# robot_board.net
KiCad netlist of a schematic drawn in EAGLE
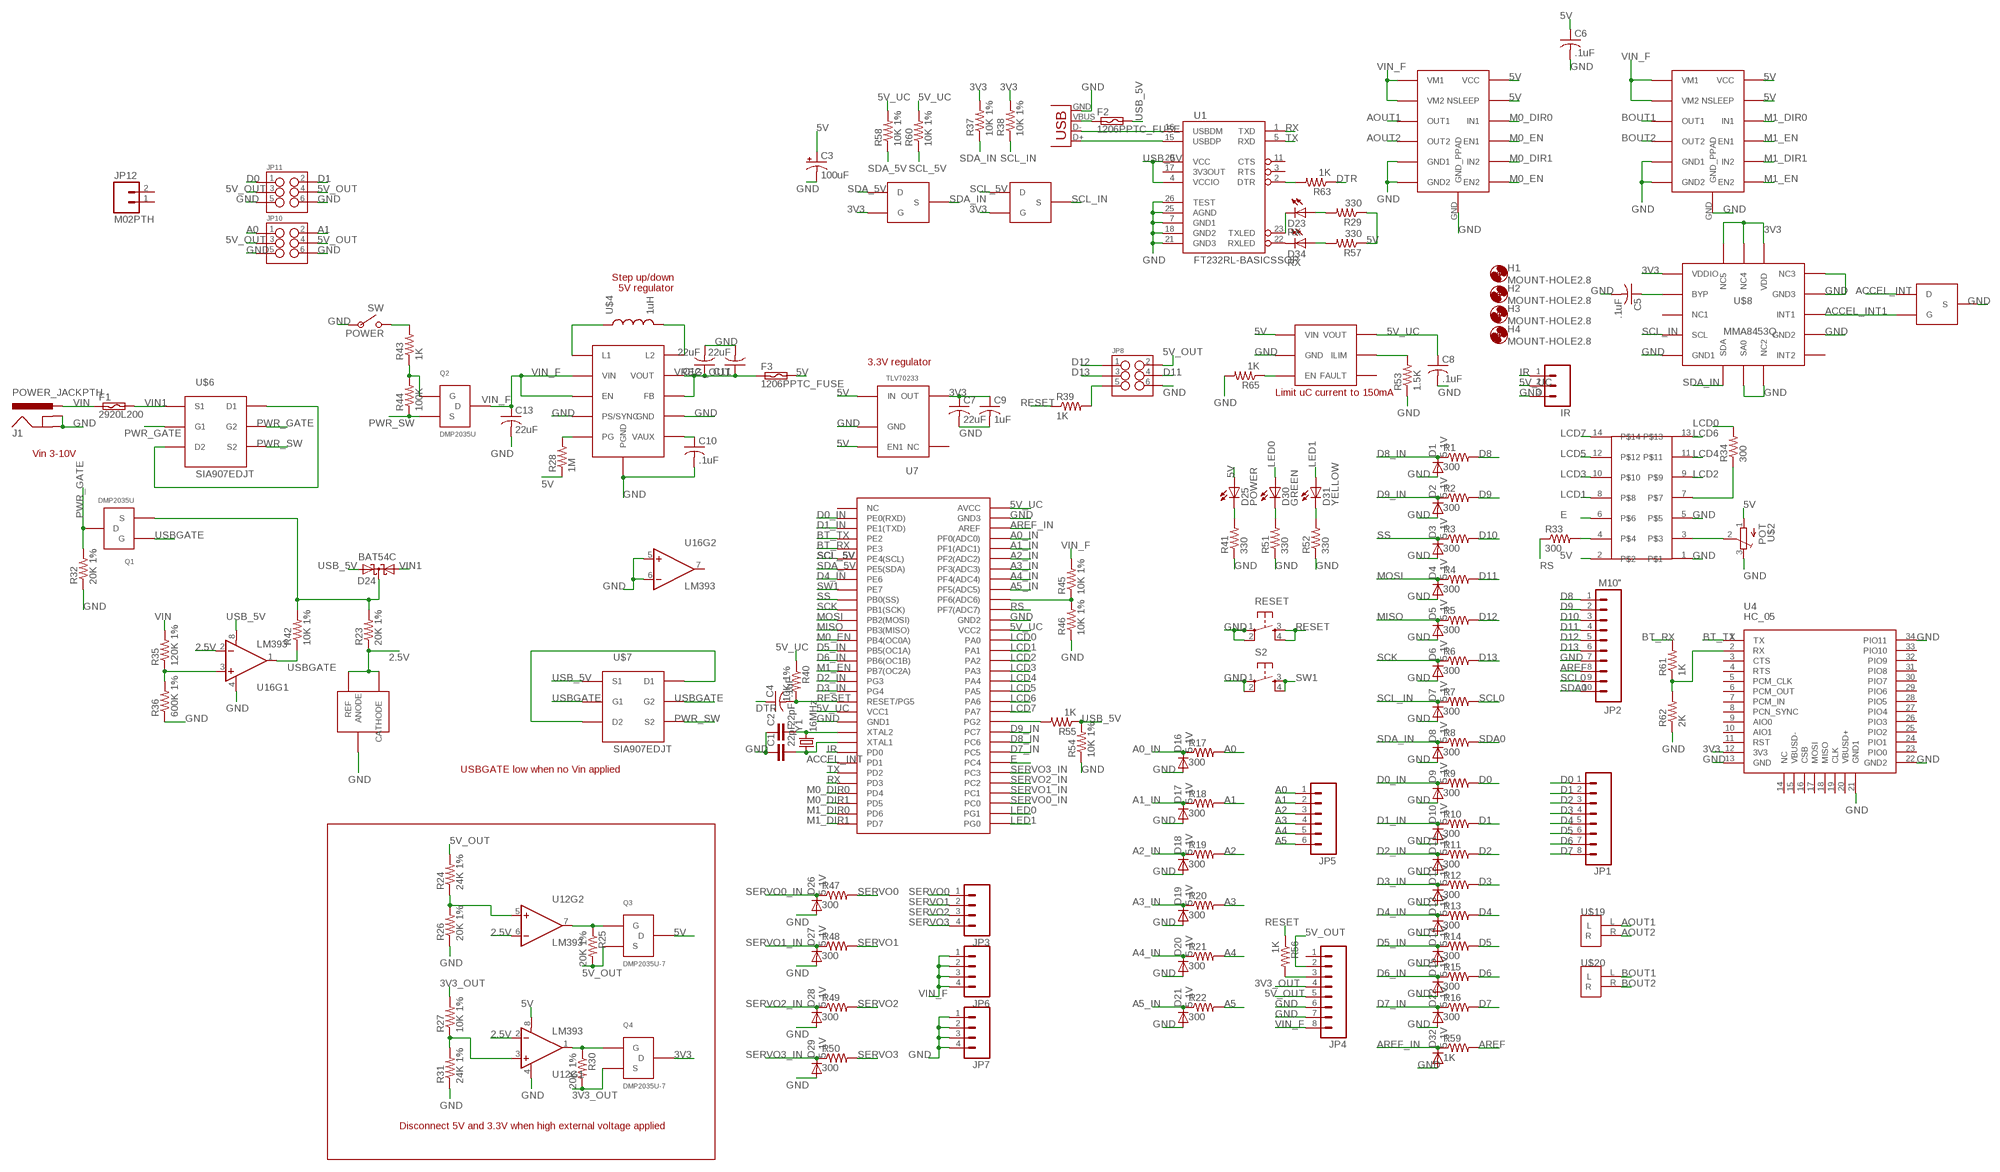
[diagram p0: schematic, sheet 1]

(export (version "E")
  (design (tool "Eeschema 10.0.6"))
  (components
    (comp (ref "C1")
      (value "22pF")
      (footprint "eagle-import:0805")
      (libsource (lib "eagle-import") (part "CAP0805"))
    )
    (comp (ref "C2")
      (value "22pF")
      (footprint "eagle-import:0805")
      (libsource (lib "eagle-import") (part "CAP0805"))
    )
    (comp (ref "C3")
      (value "100uF")
      (footprint "eagle-import:PANASONIC_D")
      (libsource (lib "eagle-import") (part "CAP_POLD"))
    )
    (comp (ref "C4")
      (value ".1uF")
      (footprint "eagle-import:C1206")
      (libsource (lib "eagle-import") (part "C-USC1206"))
    )
    (comp (ref "C5")
      (value ".1uF")
      (footprint "eagle-import:C1206")
      (libsource (lib "eagle-import") (part "C-USC1206"))
    )
    (comp (ref "C6")
      (value ".1uF")
      (footprint "eagle-import:C1206")
      (libsource (lib "eagle-import") (part "C-USC1206"))
    )
    (comp (ref "C7")
      (value "22uF")
      (footprint "eagle-import:C1206")
      (libsource (lib "eagle-import") (part "C-USC1206"))
    )
    (comp (ref "C8")
      (value ".1uF")
      (footprint "eagle-import:C1206")
      (libsource (lib "eagle-import") (part "C-USC1206"))
    )
    (comp (ref "C9")
      (value "1uF")
      (footprint "eagle-import:C1206")
      (libsource (lib "eagle-import") (part "C-USC1206"))
    )
    (comp (ref "C10")
      (value ".1uF")
      (footprint "eagle-import:C1206")
      (libsource (lib "eagle-import") (part "C-USC1206"))
    )
    (comp (ref "C11")
      (value "22uF")
      (footprint "eagle-import:C1206")
      (libsource (lib "eagle-import") (part "C-USC1206"))
    )
    (comp (ref "C12")
      (value "22uF")
      (footprint "eagle-import:C1206")
      (libsource (lib "eagle-import") (part "C-USC1206"))
    )
    (comp (ref "C13")
      (value "22uF")
      (footprint "eagle-import:C1206")
      (libsource (lib "eagle-import") (part "C-USC1206"))
    )
    (comp (ref "D1")
      (value "5.1V")
      (footprint "eagle-import:SOT23-3")
      (libsource (lib "eagle-import") (part "DIODESOT23"))
    )
    (comp (ref "D2")
      (value "5.1V")
      (footprint "eagle-import:SOT23-3")
      (libsource (lib "eagle-import") (part "DIODESOT23"))
    )
    (comp (ref "D3")
      (value "5.1V")
      (footprint "eagle-import:SOT23-3")
      (libsource (lib "eagle-import") (part "DIODESOT23"))
    )
    (comp (ref "D4")
      (value "5.1V")
      (footprint "eagle-import:SOT23-3")
      (libsource (lib "eagle-import") (part "DIODESOT23"))
    )
    (comp (ref "D5")
      (value "5.1V")
      (footprint "eagle-import:SOT23-3")
      (libsource (lib "eagle-import") (part "DIODESOT23"))
    )
    (comp (ref "D6")
      (value "5.1V")
      (footprint "eagle-import:SOT23-3")
      (libsource (lib "eagle-import") (part "DIODESOT23"))
    )
    (comp (ref "D7")
      (value "5.1V")
      (footprint "eagle-import:SOT23-3")
      (libsource (lib "eagle-import") (part "DIODESOT23"))
    )
    (comp (ref "D8")
      (value "5.1V")
      (footprint "eagle-import:SOT23-3")
      (libsource (lib "eagle-import") (part "DIODESOT23"))
    )
    (comp (ref "D9")
      (value "5.1V")
      (footprint "eagle-import:SOT23-3")
      (libsource (lib "eagle-import") (part "DIODESOT23"))
    )
    (comp (ref "D10")
      (value "5.1V")
      (footprint "eagle-import:SOT23-3")
      (libsource (lib "eagle-import") (part "DIODESOT23"))
    )
    (comp (ref "D11")
      (value "5.1V")
      (footprint "eagle-import:SOT23-3")
      (libsource (lib "eagle-import") (part "DIODESOT23"))
    )
    (comp (ref "D12")
      (value "5.1V")
      (footprint "eagle-import:SOT23-3")
      (libsource (lib "eagle-import") (part "DIODESOT23"))
    )
    (comp (ref "D13")
      (value "5.1V")
      (footprint "eagle-import:SOT23-3")
      (libsource (lib "eagle-import") (part "DIODESOT23"))
    )
    (comp (ref "D14")
      (value "5.1V")
      (footprint "eagle-import:SOT23-3")
      (libsource (lib "eagle-import") (part "DIODESOT23"))
    )
    (comp (ref "D15")
      (value "5.1V")
      (footprint "eagle-import:SOT23-3")
      (libsource (lib "eagle-import") (part "DIODESOT23"))
    )
    (comp (ref "D16")
      (value "5.1V")
      (footprint "eagle-import:SOT23-3")
      (libsource (lib "eagle-import") (part "DIODESOT23"))
    )
    (comp (ref "D17")
      (value "5.1V")
      (footprint "eagle-import:SOT23-3")
      (libsource (lib "eagle-import") (part "DIODESOT23"))
    )
    (comp (ref "D18")
      (value "5.1V")
      (footprint "eagle-import:SOT23-3")
      (libsource (lib "eagle-import") (part "DIODESOT23"))
    )
    (comp (ref "D19")
      (value "5.1V")
      (footprint "eagle-import:SOT23-3")
      (libsource (lib "eagle-import") (part "DIODESOT23"))
    )
    (comp (ref "D20")
      (value "5.1V")
      (footprint "eagle-import:SOT23-3")
      (libsource (lib "eagle-import") (part "DIODESOT23"))
    )
    (comp (ref "D21")
      (value "5.1V")
      (footprint "eagle-import:SOT23-3")
      (libsource (lib "eagle-import") (part "DIODESOT23"))
    )
    (comp (ref "D22")
      (value "5.1V")
      (footprint "eagle-import:SOT23-3")
      (libsource (lib "eagle-import") (part "DIODESOT23"))
    )
    (comp (ref "D23")
      (value "RX")
      (footprint "eagle-import:LED-1206")
      (libsource (lib "eagle-import") (part "LED-GREENLILYPAD"))
    )
    (comp (ref "D24")
      (value "BAT54C")
      (footprint "eagle-import:SOT23")
      (libsource (lib "eagle-import") (part "BAT54C"))
    )
    (comp (ref "D25")
      (value "POWER")
      (footprint "eagle-import:LED-1206")
      (libsource (lib "eagle-import") (part "LED-GREENLILYPAD"))
    )
    (comp (ref "D26")
      (value "5.1V")
      (footprint "eagle-import:SOT23-3")
      (libsource (lib "eagle-import") (part "DIODESOT23"))
    )
    (comp (ref "D27")
      (value "5.1V")
      (footprint "eagle-import:SOT23-3")
      (libsource (lib "eagle-import") (part "DIODESOT23"))
    )
    (comp (ref "D28")
      (value "5.1V")
      (footprint "eagle-import:SOT23-3")
      (libsource (lib "eagle-import") (part "DIODESOT23"))
    )
    (comp (ref "D29")
      (value "5.1V")
      (footprint "eagle-import:SOT23-3")
      (libsource (lib "eagle-import") (part "DIODESOT23"))
    )
    (comp (ref "D30")
      (value "GREEN")
      (footprint "eagle-import:LED-1206")
      (libsource (lib "eagle-import") (part "LED-GREENLILYPAD"))
    )
    (comp (ref "D31")
      (value "YELLOW")
      (footprint "eagle-import:LED-1206")
      (libsource (lib "eagle-import") (part "LED-GREENLILYPAD"))
    )
    (comp (ref "D32")
      (value "5.1V")
      (footprint "eagle-import:SOT23-3")
      (libsource (lib "eagle-import") (part "DIODESOT23"))
    )
    (comp (ref "D34")
      (value "RX")
      (footprint "eagle-import:LED-1206")
      (libsource (lib "eagle-import") (part "LED-GREENLILYPAD"))
    )
    (comp (ref "F1")
      (value "2920L200")
      (footprint "eagle-import:SMD050F")
      (libsource (lib "eagle-import") (part "2920L200"))
    )
    (comp (ref "F2")
      (value "1206PPTC_FUSE")
      (footprint "eagle-import:R1206")
      (libsource (lib "eagle-import") (part "1206PPTC_FUSE"))
    )
    (comp (ref "F3")
      (value "1206PPTC_FUSE")
      (footprint "eagle-import:R1206")
      (libsource (lib "eagle-import") (part "1206PPTC_FUSE"))
    )
    (comp (ref "H1")
      (value "MOUNT-HOLE2.8")
      (footprint "eagle-import:2,8")
      (libsource (lib "eagle-import") (part "MOUNT-HOLE2.8"))
    )
    (comp (ref "H2")
      (value "MOUNT-HOLE2.8")
      (footprint "eagle-import:2,8")
      (libsource (lib "eagle-import") (part "MOUNT-HOLE2.8"))
    )
    (comp (ref "H3")
      (value "MOUNT-HOLE2.8")
      (footprint "eagle-import:2,8")
      (libsource (lib "eagle-import") (part "MOUNT-HOLE2.8"))
    )
    (comp (ref "H4")
      (value "MOUNT-HOLE2.8")
      (footprint "eagle-import:2,8")
      (libsource (lib "eagle-import") (part "MOUNT-HOLE2.8"))
    )
    (comp (ref "IR")
      (value "M03PTH")
      (footprint "eagle-import:1X03")
      (libsource (lib "eagle-import") (part "M03PTH"))
    )
    (comp (ref "J1")
      (value "POWER_JACKPTH")
      (footprint "eagle-import:POWER_JACK_PTH")
      (libsource (lib "eagle-import") (part "POWER_JACKPTH"))
    )
    (comp (ref "JP1")
      (value "M081X08")
      (footprint "eagle-import:1X08")
      (libsource (lib "eagle-import") (part "M081X08"))
    )
    (comp (ref "JP2")
      (value "M10\"")
      (footprint "eagle-import:1X10")
      (libsource (lib "eagle-import") (part "M10{dblquote}"))
    )
    (comp (ref "JP3")
      (value "M04PTH")
      (footprint "eagle-import:1X04")
      (libsource (lib "eagle-import") (part "M04PTH"))
    )
    (comp (ref "JP4")
      (value "M081X08")
      (footprint "eagle-import:1X08")
      (libsource (lib "eagle-import") (part "M081X08"))
    )
    (comp (ref "JP5")
      (value "M06SIP")
      (footprint "eagle-import:1X06")
      (libsource (lib "eagle-import") (part "M06SIP"))
    )
    (comp (ref "JP6")
      (value "M04PTH")
      (footprint "eagle-import:1X04")
      (libsource (lib "eagle-import") (part "M04PTH"))
    )
    (comp (ref "JP7")
      (value "M04PTH")
      (footprint "eagle-import:1X04")
      (libsource (lib "eagle-import") (part "M04PTH"))
    )
    (comp (ref "JP8")
      (value "M03X22X3_SILK_SM")
      (footprint "eagle-import:2X3")
      (libsource (lib "eagle-import") (part "M03X22X3_SILK_SM"))
    )
    (comp (ref "JP9")
      (value "USB-B")
      (footprint "eagle-import:USB-B-PTH")
      (libsource (lib "eagle-import") (part "USBPTH"))
    )
    (comp (ref "JP10")
      (value "M03X22X3_SILK_SM")
      (footprint "eagle-import:2X3")
      (libsource (lib "eagle-import") (part "M03X22X3_SILK_SM"))
    )
    (comp (ref "JP11")
      (value "M03X22X3_SILK_SM")
      (footprint "eagle-import:2X3")
      (libsource (lib "eagle-import") (part "M03X22X3_SILK_SM"))
    )
    (comp (ref "JP12")
      (value "M02PTH")
      (footprint "eagle-import:1X02")
      (libsource (lib "eagle-import") (part "M02PTH"))
    )
    (comp (ref "POWER")
      (value "SW")
      (footprint "eagle-import:SW")
      (libsource (lib "eagle-import") (part "SW"))
    )
    (comp (ref "Q1")
      (value "DMP2035U")
      (footprint "eagle-import:SOT23")
      (libsource (lib "eagle-import") (part "DMP2035U"))
    )
    (comp (ref "Q2")
      (value "DMP2035U")
      (footprint "eagle-import:SOT23")
      (libsource (lib "eagle-import") (part "DMP2035U"))
    )
    (comp (ref "Q3")
      (value "DMP2035U-7")
      (footprint "eagle-import:SOT23@1")
      (libsource (lib "eagle-import") (part "DMP2035U-7"))
    )
    (comp (ref "Q4")
      (value "DMP2035U-7")
      (footprint "eagle-import:SOT23@1")
      (libsource (lib "eagle-import") (part "DMP2035U-7"))
    )
    (comp (ref "R1")
      (value "300")
      (footprint "eagle-import:R1206")
      (libsource (lib "eagle-import") (part "R-US_R1206"))
    )
    (comp (ref "R2")
      (value "300")
      (footprint "eagle-import:R1206")
      (libsource (lib "eagle-import") (part "R-US_R1206"))
    )
    (comp (ref "R3")
      (value "300")
      (footprint "eagle-import:R1206")
      (libsource (lib "eagle-import") (part "R-US_R1206"))
    )
    (comp (ref "R4")
      (value "300")
      (footprint "eagle-import:R1206")
      (libsource (lib "eagle-import") (part "R-US_R1206"))
    )
    (comp (ref "R5")
      (value "300")
      (footprint "eagle-import:R1206")
      (libsource (lib "eagle-import") (part "R-US_R1206"))
    )
    (comp (ref "R6")
      (value "300")
      (footprint "eagle-import:R1206")
      (libsource (lib "eagle-import") (part "R-US_R1206"))
    )
    (comp (ref "R7")
      (value "300")
      (footprint "eagle-import:R1206")
      (libsource (lib "eagle-import") (part "R-US_R1206"))
    )
    (comp (ref "R8")
      (value "300")
      (footprint "eagle-import:R1206")
      (libsource (lib "eagle-import") (part "R-US_R1206"))
    )
    (comp (ref "R9")
      (value "300")
      (footprint "eagle-import:R1206")
      (libsource (lib "eagle-import") (part "R-US_R1206"))
    )
    (comp (ref "R10")
      (value "300")
      (footprint "eagle-import:R1206")
      (libsource (lib "eagle-import") (part "R-US_R1206"))
    )
    (comp (ref "R11")
      (value "300")
      (footprint "eagle-import:R1206")
      (libsource (lib "eagle-import") (part "R-US_R1206"))
    )
    (comp (ref "R12")
      (value "300")
      (footprint "eagle-import:R1206")
      (libsource (lib "eagle-import") (part "R-US_R1206"))
    )
    (comp (ref "R13")
      (value "300")
      (footprint "eagle-import:R1206")
      (libsource (lib "eagle-import") (part "R-US_R1206"))
    )
    (comp (ref "R14")
      (value "300")
      (footprint "eagle-import:R1206")
      (libsource (lib "eagle-import") (part "R-US_R1206"))
    )
    (comp (ref "R15")
      (value "300")
      (footprint "eagle-import:R1206")
      (libsource (lib "eagle-import") (part "R-US_R1206"))
    )
    (comp (ref "R16")
      (value "300")
      (footprint "eagle-import:R1206")
      (libsource (lib "eagle-import") (part "R-US_R1206"))
    )
    (comp (ref "R17")
      (value "300")
      (footprint "eagle-import:R1206")
      (libsource (lib "eagle-import") (part "R-US_R1206"))
    )
    (comp (ref "R18")
      (value "300")
      (footprint "eagle-import:R1206")
      (libsource (lib "eagle-import") (part "R-US_R1206"))
    )
    (comp (ref "R19")
      (value "300")
      (footprint "eagle-import:R1206")
      (libsource (lib "eagle-import") (part "R-US_R1206"))
    )
    (comp (ref "R20")
      (value "300")
      (footprint "eagle-import:R1206")
      (libsource (lib "eagle-import") (part "R-US_R1206"))
    )
    (comp (ref "R21")
      (value "300")
      (footprint "eagle-import:R1206")
      (libsource (lib "eagle-import") (part "R-US_R1206"))
    )
    (comp (ref "R22")
      (value "300")
      (footprint "eagle-import:R1206")
      (libsource (lib "eagle-import") (part "R-US_R1206"))
    )
    (comp (ref "R23")
      (value "20K 1%")
      (footprint "eagle-import:R1206")
      (libsource (lib "eagle-import") (part "R-US_R1206"))
    )
    (comp (ref "R24")
      (value "24K 1%")
      (footprint "eagle-import:R1206")
      (libsource (lib "eagle-import") (part "R-US_R1206"))
    )
    (comp (ref "R25")
      (value "20K 1%")
      (footprint "eagle-import:R1206")
      (libsource (lib "eagle-import") (part "R-US_R1206"))
    )
    (comp (ref "R26")
      (value "20K 1%")
      (footprint "eagle-import:R1206")
      (libsource (lib "eagle-import") (part "R-US_R1206"))
    )
    (comp (ref "R27")
      (value "10K 1%")
      (footprint "eagle-import:R1206")
      (libsource (lib "eagle-import") (part "R-US_R1206"))
    )
    (comp (ref "R28")
      (value "1M")
      (footprint "eagle-import:R1206")
      (libsource (lib "eagle-import") (part "R-US_R1206"))
    )
    (comp (ref "R29")
      (value "330")
      (footprint "eagle-import:R1206")
      (libsource (lib "eagle-import") (part "R-US_R1206"))
    )
    (comp (ref "R30")
      (value "20K 1%")
      (footprint "eagle-import:R1206")
      (libsource (lib "eagle-import") (part "R-US_R1206"))
    )
    (comp (ref "R31")
      (value "24K 1%")
      (footprint "eagle-import:R1206")
      (libsource (lib "eagle-import") (part "R-US_R1206"))
    )
    (comp (ref "R32")
      (value "20K 1%")
      (footprint "eagle-import:R1206")
      (libsource (lib "eagle-import") (part "R-US_R1206"))
    )
    (comp (ref "R33")
      (value "300")
      (footprint "eagle-import:R1206")
      (libsource (lib "eagle-import") (part "R-US_R1206"))
    )
    (comp (ref "R34")
      (value "300")
      (footprint "eagle-import:R1206")
      (libsource (lib "eagle-import") (part "R-US_R1206"))
    )
    (comp (ref "R35")
      (value "120K 1%")
      (footprint "eagle-import:R1206")
      (libsource (lib "eagle-import") (part "R-US_R1206"))
    )
    (comp (ref "R36")
      (value "600K 1%")
      (footprint "eagle-import:R1206")
      (libsource (lib "eagle-import") (part "R-US_R1206"))
    )
    (comp (ref "R37")
      (value "10K 1%")
      (footprint "eagle-import:R1206")
      (libsource (lib "eagle-import") (part "R-US_R1206"))
    )
    (comp (ref "R38")
      (value "10K 1%")
      (footprint "eagle-import:R1206")
      (libsource (lib "eagle-import") (part "R-US_R1206"))
    )
    (comp (ref "R39")
      (value "1K")
      (footprint "eagle-import:R1206")
      (libsource (lib "eagle-import") (part "R-US_R1206"))
    )
    (comp (ref "R40")
      (value "10K 1%")
      (footprint "eagle-import:R1206")
      (libsource (lib "eagle-import") (part "R-US_R1206"))
    )
    (comp (ref "R41")
      (value "330")
      (footprint "eagle-import:R1206")
      (libsource (lib "eagle-import") (part "R-US_R1206"))
    )
    (comp (ref "R42")
      (value "10K 1%")
      (footprint "eagle-import:R1206")
      (libsource (lib "eagle-import") (part "R-US_R1206"))
    )
    (comp (ref "R43")
      (value "1K")
      (footprint "eagle-import:R1206")
      (libsource (lib "eagle-import") (part "R-US_R1206"))
    )
    (comp (ref "R44")
      (value "100K")
      (footprint "eagle-import:R1206")
      (libsource (lib "eagle-import") (part "R-US_R1206"))
    )
    (comp (ref "R45")
      (value "10K 1%")
      (footprint "eagle-import:R1206")
      (libsource (lib "eagle-import") (part "R-US_R1206"))
    )
    (comp (ref "R46")
      (value "10K 1%")
      (footprint "eagle-import:R1206")
      (libsource (lib "eagle-import") (part "R-US_R1206"))
    )
    (comp (ref "R47")
      (value "300")
      (footprint "eagle-import:R1206")
      (libsource (lib "eagle-import") (part "R-US_R1206"))
    )
    (comp (ref "R48")
      (value "300")
      (footprint "eagle-import:R1206")
      (libsource (lib "eagle-import") (part "R-US_R1206"))
    )
    (comp (ref "R49")
      (value "300")
      (footprint "eagle-import:R1206")
      (libsource (lib "eagle-import") (part "R-US_R1206"))
    )
    (comp (ref "R50")
      (value "300")
      (footprint "eagle-import:R1206")
      (libsource (lib "eagle-import") (part "R-US_R1206"))
    )
    (comp (ref "R51")
      (value "330")
      (footprint "eagle-import:R1206")
      (libsource (lib "eagle-import") (part "R-US_R1206"))
    )
    (comp (ref "R52")
      (value "330")
      (footprint "eagle-import:R1206")
      (libsource (lib "eagle-import") (part "R-US_R1206"))
    )
    (comp (ref "R53")
      (value "1.5K")
      (footprint "eagle-import:R1206")
      (libsource (lib "eagle-import") (part "R-US_R1206"))
    )
    (comp (ref "R54")
      (value "10K 1%")
      (footprint "eagle-import:R1206")
      (libsource (lib "eagle-import") (part "R-US_R1206"))
    )
    (comp (ref "R55")
      (value "1K")
      (footprint "eagle-import:R1206")
      (libsource (lib "eagle-import") (part "R-US_R1206"))
    )
    (comp (ref "R56")
      (value "1K")
      (footprint "eagle-import:R1206")
      (libsource (lib "eagle-import") (part "R-US_R1206"))
    )
    (comp (ref "R57")
      (value "330")
      (footprint "eagle-import:R1206")
      (libsource (lib "eagle-import") (part "R-US_R1206"))
    )
    (comp (ref "R58")
      (value "10K 1%")
      (footprint "eagle-import:R1206")
      (libsource (lib "eagle-import") (part "R-US_R1206"))
    )
    (comp (ref "R59")
      (value "1K")
      (footprint "eagle-import:R1206")
      (libsource (lib "eagle-import") (part "R-US_R1206"))
    )
    (comp (ref "R60")
      (value "10K 1%")
      (footprint "eagle-import:R1206")
      (libsource (lib "eagle-import") (part "R-US_R1206"))
    )
    (comp (ref "R61")
      (value "1K")
      (footprint "eagle-import:R1206")
      (libsource (lib "eagle-import") (part "R-US_R1206"))
    )
    (comp (ref "R62")
      (value "2K")
      (footprint "eagle-import:R1206")
      (libsource (lib "eagle-import") (part "R-US_R1206"))
    )
    (comp (ref "R63")
      (value "1K")
      (footprint "eagle-import:R1206")
      (libsource (lib "eagle-import") (part "R-US_R1206"))
    )
    (comp (ref "R65")
      (value "1K")
      (footprint "eagle-import:R1206")
      (libsource (lib "eagle-import") (part "R-US_R1206"))
    )
    (comp (ref "RESET")
      (value "TAC_SWITCHPTH")
      (footprint "eagle-import:TACTILE-PTH")
      (libsource (lib "eagle-import") (part "TAC_SWITCHPTH"))
    )
    (comp (ref "S2")
      (value "TAC_SWITCHPTH")
      (footprint "eagle-import:TACTILE-PTH")
      (libsource (lib "eagle-import") (part "TAC_SWITCHPTH"))
    )
    (comp (ref "U$1")
      (value "2X7HEADER")
      (footprint "eagle-import:2X7")
      (libsource (lib "eagle-import") (part "2X7HEADER"))
    )
    (comp (ref "U$2")
      (value "POT")
      (footprint "eagle-import:POT")
      (libsource (lib "eagle-import") (part "POT"))
    )
    (comp (ref "U$3")
      (value "TPS63061")
      (footprint "eagle-import:WSON-10")
      (libsource (lib "eagle-import") (part "TPS63061"))
    )
    (comp (ref "U$4")
      (value "1uH")
      (footprint "eagle-import:TAIYO4012")
      (libsource (lib "eagle-import") (part "TAIYO4012"))
    )
    (comp (ref "U$5")
      (value "AP431SAG-7")
      (footprint "eagle-import:SOT23")
      (libsource (lib "eagle-import") (part "AP431SAG-7"))
    )
    (comp (ref "U$6")
      (value "SIA907EDJT")
      (footprint "eagle-import:SC70T")
      (libsource (lib "eagle-import") (part "SIA907EDJT"))
    )
    (comp (ref "U$7")
      (value "SIA907EDJT")
      (footprint "eagle-import:SC70T")
      (libsource (lib "eagle-import") (part "SIA907EDJT"))
    )
    (comp (ref "U$8")
      (value "MMA8453Q")
      (footprint "eagle-import:QFN-COL")
      (libsource (lib "eagle-import") (part "MMA8453Q"))
    )
    (comp (ref "U$9")
      (value "BSS138")
      (footprint "eagle-import:SOT23")
      (libsource (lib "eagle-import") (part "BSS138"))
    )
    (comp (ref "U$10")
      (value "BSS138")
      (footprint "eagle-import:SOT23")
      (libsource (lib "eagle-import") (part "BSS138"))
    )
    (comp (ref "U$11")
      (value "BSS138")
      (footprint "eagle-import:SOT23")
      (libsource (lib "eagle-import") (part "BSS138"))
    )
    (comp (ref "U$19")
      (value "2POS_TERMINAL")
      (footprint "eagle-import:2POS_TERMINAL")
      (libsource (lib "eagle-import") (part "2POS_TERMINAL"))
    )
    (comp (ref "U$20")
      (value "2POS_TERMINAL")
      (footprint "eagle-import:2POS_TERMINAL")
      (libsource (lib "eagle-import") (part "2POS_TERMINAL"))
    )
    (comp (ref "U1")
      (value "FT232RL-BASICSSOP")
      (footprint "eagle-import:SSOP28DB")
      (libsource (lib "eagle-import") (part "FT232RL-BASICSSOP"))
    )
    (comp (ref "U4")
      (value "HC_05")
      (footprint "eagle-import:BLUETOOTH_SMD")
      (libsource (lib "eagle-import") (part "HC_05"))
    )
    (comp (ref "U7")
      (value "TLV70233")
      (footprint "eagle-import:SOT-23-5")
      (libsource (lib "eagle-import") (part "TLV70233"))
    )
    (comp (ref "U8")
      (value "MIC2009A")
      (footprint "eagle-import:SOT23-M5")
      (libsource (lib "eagle-import") (part "MIC2009A"))
    )
    (comp (ref "U9")
      (value "DRV8839")
      (footprint "eagle-import:PWSON-N12")
      (libsource (lib "eagle-import") (part "DRV8839"))
    )
    (comp (ref "U10")
      (value "DRV8839")
      (footprint "eagle-import:PWSON-N12")
      (libsource (lib "eagle-import") (part "DRV8839"))
    )
    (comp (ref "U12")
      (value "LM393")
      (footprint "eagle-import:SO08")
      (libsource (lib "eagle-import") (part "LM393"))
    )
    (comp (ref "U16")
      (value "LM393")
      (footprint "eagle-import:SO08")
      (libsource (lib "eagle-import") (part "LM393"))
    )
    (comp (ref "U17")
      (value "ATMEGA325PA")
      (footprint "eagle-import:TQFP64")
      (libsource (lib "eagle-import") (part "ATMEGA325PA"))
    )
    (comp (ref "Y1")
      (value "16MHz")
      (footprint "eagle-import:CRYSTAL-SMD-10.5X4.8-2PIN")
      (libsource (lib "eagle-import") (part "CRYSTAL10.5X4.8"))
    )
  )
  (nets
    (net (code "1") (name "/2.5V") (class "Default")
      (node (ref "R23") (pin "1") (pinfunction "1_1") (pintype "passive"))
      (node (ref "U$5") (pin "1") (pinfunction "CATHODE_1") (pintype "bidirectional"))
      (node (ref "U$5") (pin "2") (pinfunction "REF_2") (pintype "bidirectional"))
      (node (ref "U12") (pin "2") (pinfunction "-IN_2") (pintype "input"))
      (node (ref "U12") (pin "6") (pinfunction "-IN_6") (pintype "input"))
      (node (ref "U16") (pin "2") (pinfunction "-IN_2") (pintype "input"))
    )
    (net (code "2") (name "/3V3") (class "Default")
      (node (ref "C7") (pin "1") (pinfunction "1_1") (pintype "passive"))
      (node (ref "C9") (pin "1") (pinfunction "1_1") (pintype "passive"))
      (node (ref "Q4") (pin "3") (pinfunction "D_3") (pintype "bidirectional"))
      (node (ref "R37") (pin "2") (pinfunction "2_2") (pintype "passive"))
      (node (ref "R38") (pin "2") (pinfunction "2_2") (pintype "passive"))
      (node (ref "U$10") (pin "1") (pinfunction "G_1") (pintype "bidirectional"))
      (node (ref "U$8") (pin "P$1") (pinfunction "VDDIO_P$1") (pintype "bidirectional"))
      (node (ref "U$8") (pin "P$14") (pinfunction "VDD_P$14") (pintype "bidirectional"))
      (node (ref "U$8") (pin "P$15") (pinfunction "NC4_P$15") (pintype "bidirectional"))
      (node (ref "U$8") (pin "P$16") (pinfunction "NC5_P$16") (pintype "bidirectional"))
      (node (ref "U$9") (pin "1") (pinfunction "G_1") (pintype "bidirectional"))
      (node (ref "U4") (pin "12") (pinfunction "3V3_12") (pintype "bidirectional"))
      (node (ref "U7") (pin "P$4") (pinfunction "OUT_P$4") (pintype "bidirectional"))
    )
    (net (code "3") (name "/3V3_OUT") (class "Default")
      (node (ref "JP4") (pin "4") (pinfunction "4_4") (pintype "passive"))
      (node (ref "Q4") (pin "2") (pinfunction "S_2") (pintype "bidirectional"))
      (node (ref "R27") (pin "2") (pinfunction "2_2") (pintype "passive"))
      (node (ref "R30") (pin "2") (pinfunction "2_2") (pintype "passive"))
    )
    (net (code "4") (name "/5V") (class "Default")
      (node (ref "C3") (pin "+") (pinfunction "+_+") (pintype "passive"))
      (node (ref "C6") (pin "1") (pinfunction "1_1") (pintype "passive"))
      (node (ref "D25") (pin "A") (pinfunction "A_A") (pintype "passive"))
      (node (ref "F3") (pin "2") (pinfunction "2_2") (pintype "passive"))
      (node (ref "Q3") (pin "3") (pinfunction "D_3") (pintype "bidirectional"))
      (node (ref "R28") (pin "1") (pinfunction "1_1") (pintype "passive"))
      (node (ref "R29") (pin "1") (pinfunction "1_1") (pintype "passive"))
      (node (ref "R57") (pin "1") (pinfunction "1_1") (pintype "passive"))
      (node (ref "U$1") (pin "2") (pinfunction "P$2_2") (pintype "bidirectional"))
      (node (ref "U$2") (pin "1") (pinfunction "A_1") (pintype "passive"))
      (node (ref "U10") (pin "P$7") (pinfunction "VCC_P$7") (pintype "bidirectional"))
      (node (ref "U10") (pin "P$8") (pinfunction "NSLEEP_P$8") (pintype "bidirectional"))
      (node (ref "U12") (pin "8") (pinfunction "V+_8") (pintype "power_in"))
      (node (ref "U7") (pin "P$1") (pinfunction "IN_P$1") (pintype "bidirectional"))
      (node (ref "U7") (pin "P$3") (pinfunction "EN1_P$3") (pintype "bidirectional"))
      (node (ref "U8") (pin "P$1") (pinfunction "VIN_P$1") (pintype "bidirectional"))
      (node (ref "U9") (pin "P$7") (pinfunction "VCC_P$7") (pintype "bidirectional"))
      (node (ref "U9") (pin "P$8") (pinfunction "NSLEEP_P$8") (pintype "bidirectional"))
    )
    (net (code "5") (name "/5V_OUT") (class "Default")
      (node (ref "JP10") (pin "3") (pinfunction "3_3") (pintype "bidirectional"))
      (node (ref "JP10") (pin "4") (pinfunction "4_4") (pintype "bidirectional"))
      (node (ref "JP11") (pin "3") (pinfunction "3_3") (pintype "bidirectional"))
      (node (ref "JP11") (pin "4") (pinfunction "4_4") (pintype "bidirectional"))
      (node (ref "JP4") (pin "2") (pinfunction "2_2") (pintype "passive"))
      (node (ref "JP4") (pin "5") (pinfunction "5_5") (pintype "passive"))
      (node (ref "JP8") (pin "2") (pinfunction "2_2") (pintype "bidirectional"))
      (node (ref "Q3") (pin "2") (pinfunction "S_2") (pintype "bidirectional"))
      (node (ref "R24") (pin "2") (pinfunction "2_2") (pintype "passive"))
      (node (ref "R25") (pin "2") (pinfunction "2_2") (pintype "passive"))
    )
    (net (code "6") (name "/5V_UC") (class "Default")
      (node (ref "C8") (pin "1") (pinfunction "1_1") (pintype "passive"))
      (node (ref "IR") (pin "2") (pinfunction "2_2") (pintype "passive"))
      (node (ref "R40") (pin "1") (pinfunction "1_1") (pintype "passive"))
      (node (ref "R58") (pin "2") (pinfunction "2_2") (pintype "passive"))
      (node (ref "R60") (pin "2") (pinfunction "2_2") (pintype "passive"))
      (node (ref "U17") (pin "21") (pinfunction "VCC1_21") (pintype "bidirectional"))
      (node (ref "U17") (pin "52") (pinfunction "VCC2_52") (pintype "bidirectional"))
      (node (ref "U17") (pin "64") (pinfunction "AVCC_64") (pintype "bidirectional"))
      (node (ref "U8") (pin "P$6") (pinfunction "VOUT_P$6") (pintype "bidirectional"))
    )
    (net (code "7") (name "/A0") (class "Default")
      (node (ref "JP10") (pin "1") (pinfunction "1_1") (pintype "bidirectional"))
      (node (ref "JP5") (pin "1") (pinfunction "1_1") (pintype "passive"))
      (node (ref "R17") (pin "2") (pinfunction "2_2") (pintype "passive"))
    )
    (net (code "8") (name "/A0_IN") (class "Default")
      (node (ref "D16") (pin "3") (pinfunction "C_3") (pintype "passive"))
      (node (ref "R17") (pin "1") (pinfunction "1_1") (pintype "passive"))
      (node (ref "U17") (pin "61") (pinfunction "PF0(ADC0)_61") (pintype "bidirectional"))
    )
    (net (code "9") (name "/A1") (class "Default")
      (node (ref "JP10") (pin "2") (pinfunction "2_2") (pintype "bidirectional"))
      (node (ref "JP5") (pin "2") (pinfunction "2_2") (pintype "passive"))
      (node (ref "R18") (pin "2") (pinfunction "2_2") (pintype "passive"))
    )
    (net (code "10") (name "/A1_IN") (class "Default")
      (node (ref "D17") (pin "3") (pinfunction "C_3") (pintype "passive"))
      (node (ref "R18") (pin "1") (pinfunction "1_1") (pintype "passive"))
      (node (ref "U17") (pin "60") (pinfunction "PF1(ADC1)_60") (pintype "bidirectional"))
    )
    (net (code "11") (name "/A2") (class "Default")
      (node (ref "JP5") (pin "3") (pinfunction "3_3") (pintype "passive"))
      (node (ref "R19") (pin "2") (pinfunction "2_2") (pintype "passive"))
    )
    (net (code "12") (name "/A2_IN") (class "Default")
      (node (ref "D18") (pin "3") (pinfunction "C_3") (pintype "passive"))
      (node (ref "R19") (pin "1") (pinfunction "1_1") (pintype "passive"))
      (node (ref "U17") (pin "59") (pinfunction "PF2(ADC2)_59") (pintype "bidirectional"))
    )
    (net (code "13") (name "/A3") (class "Default")
      (node (ref "JP5") (pin "4") (pinfunction "4_4") (pintype "passive"))
      (node (ref "R20") (pin "2") (pinfunction "2_2") (pintype "passive"))
    )
    (net (code "14") (name "/A3_IN") (class "Default")
      (node (ref "D19") (pin "3") (pinfunction "C_3") (pintype "passive"))
      (node (ref "R20") (pin "1") (pinfunction "1_1") (pintype "passive"))
      (node (ref "U17") (pin "58") (pinfunction "PF3(ADC3)_58") (pintype "bidirectional"))
    )
    (net (code "15") (name "/A4") (class "Default")
      (node (ref "JP5") (pin "5") (pinfunction "5_5") (pintype "passive"))
      (node (ref "R21") (pin "2") (pinfunction "2_2") (pintype "passive"))
    )
    (net (code "16") (name "/A4_IN") (class "Default")
      (node (ref "D20") (pin "3") (pinfunction "C_3") (pintype "passive"))
      (node (ref "R21") (pin "1") (pinfunction "1_1") (pintype "passive"))
      (node (ref "U17") (pin "57") (pinfunction "PF4(ADC4)_57") (pintype "bidirectional"))
    )
    (net (code "17") (name "/A5") (class "Default")
      (node (ref "JP5") (pin "6") (pinfunction "6_6") (pintype "passive"))
      (node (ref "R22") (pin "2") (pinfunction "2_2") (pintype "passive"))
    )
    (net (code "18") (name "/A5_IN") (class "Default")
      (node (ref "D21") (pin "3") (pinfunction "C_3") (pintype "passive"))
      (node (ref "R22") (pin "1") (pinfunction "1_1") (pintype "passive"))
      (node (ref "U17") (pin "56") (pinfunction "PF5(ADC5)_56") (pintype "bidirectional"))
    )
    (net (code "19") (name "/ACCEL_INT") (class "Default")
      (node (ref "U$11") (pin "3") (pinfunction "D_3") (pintype "bidirectional"))
      (node (ref "U17") (pin "26") (pinfunction "PD1_26") (pintype "bidirectional"))
    )
    (net (code "20") (name "/ACCEL_INT1") (class "Default")
      (node (ref "U$11") (pin "1") (pinfunction "G_1") (pintype "bidirectional"))
      (node (ref "U$8") (pin "P$11") (pinfunction "INT1_P$11") (pintype "bidirectional"))
    )
    (net (code "21") (name "/AOUT1") (class "Default")
      (node (ref "U$19") (pin "L") (pinfunction "L_L") (pintype "bidirectional"))
      (node (ref "U9") (pin "P$3") (pinfunction "OUT1_P$3") (pintype "bidirectional"))
    )
    (net (code "22") (name "/AOUT2") (class "Default")
      (node (ref "U$19") (pin "R") (pinfunction "R_R") (pintype "bidirectional"))
      (node (ref "U9") (pin "P$4") (pinfunction "OUT2_P$4") (pintype "bidirectional"))
    )
    (net (code "23") (name "/AREF") (class "Default")
      (node (ref "JP2") (pin "8") (pinfunction "8_8") (pintype "passive"))
      (node (ref "R59") (pin "2") (pinfunction "2_2") (pintype "passive"))
    )
    (net (code "24") (name "/AREF_IN") (class "Default")
      (node (ref "D32") (pin "3") (pinfunction "C_3") (pintype "passive"))
      (node (ref "R59") (pin "1") (pinfunction "1_1") (pintype "passive"))
      (node (ref "U17") (pin "62") (pinfunction "AREF_62") (pintype "bidirectional"))
    )
    (net (code "25") (name "/BOUT1") (class "Default")
      (node (ref "U$20") (pin "L") (pinfunction "L_L") (pintype "bidirectional"))
      (node (ref "U10") (pin "P$3") (pinfunction "OUT1_P$3") (pintype "bidirectional"))
    )
    (net (code "26") (name "/BOUT2") (class "Default")
      (node (ref "U$20") (pin "R") (pinfunction "R_R") (pintype "bidirectional"))
      (node (ref "U10") (pin "P$4") (pinfunction "OUT2_P$4") (pintype "bidirectional"))
    )
    (net (code "27") (name "/BT_RX") (class "Default")
      (node (ref "R61") (pin "2") (pinfunction "2_2") (pintype "passive"))
      (node (ref "U17") (pin "5") (pinfunction "PE3_5") (pintype "bidirectional"))
    )
    (net (code "28") (name "/BT_TX") (class "Default")
      (node (ref "U17") (pin "4") (pinfunction "PE2_4") (pintype "bidirectional"))
      (node (ref "U4") (pin "1") (pinfunction "TX_1") (pintype "bidirectional"))
    )
    (net (code "29") (name "/D0") (class "Default")
      (node (ref "JP1") (pin "1") (pinfunction "1_1") (pintype "passive"))
      (node (ref "JP11") (pin "1") (pinfunction "1_1") (pintype "bidirectional"))
      (node (ref "R9") (pin "2") (pinfunction "2_2") (pintype "passive"))
    )
    (net (code "30") (name "/D0_IN") (class "Default")
      (node (ref "D9") (pin "3") (pinfunction "C_3") (pintype "passive"))
      (node (ref "R9") (pin "1") (pinfunction "1_1") (pintype "passive"))
      (node (ref "U17") (pin "2") (pinfunction "PE0(RXD)_2") (pintype "bidirectional"))
    )
    (net (code "31") (name "/D1") (class "Default")
      (node (ref "JP1") (pin "2") (pinfunction "2_2") (pintype "passive"))
      (node (ref "JP11") (pin "2") (pinfunction "2_2") (pintype "bidirectional"))
      (node (ref "R10") (pin "2") (pinfunction "2_2") (pintype "passive"))
    )
    (net (code "32") (name "/D1_IN") (class "Default")
      (node (ref "D10") (pin "3") (pinfunction "C_3") (pintype "passive"))
      (node (ref "R10") (pin "1") (pinfunction "1_1") (pintype "passive"))
      (node (ref "U17") (pin "3") (pinfunction "PE1(TXD)_3") (pintype "bidirectional"))
    )
    (net (code "33") (name "/D2") (class "Default")
      (node (ref "JP1") (pin "3") (pinfunction "3_3") (pintype "passive"))
      (node (ref "R11") (pin "2") (pinfunction "2_2") (pintype "passive"))
    )
    (net (code "34") (name "/D2_IN") (class "Default")
      (node (ref "D11") (pin "3") (pinfunction "C_3") (pintype "passive"))
      (node (ref "R11") (pin "1") (pinfunction "1_1") (pintype "passive"))
      (node (ref "U17") (pin "18") (pinfunction "PG3_18") (pintype "bidirectional"))
    )
    (net (code "35") (name "/D3") (class "Default")
      (node (ref "JP1") (pin "4") (pinfunction "4_4") (pintype "passive"))
      (node (ref "R12") (pin "2") (pinfunction "2_2") (pintype "passive"))
    )
    (net (code "36") (name "/D3_IN") (class "Default")
      (node (ref "D12") (pin "3") (pinfunction "C_3") (pintype "passive"))
      (node (ref "R12") (pin "1") (pinfunction "1_1") (pintype "passive"))
      (node (ref "U17") (pin "19") (pinfunction "PG4_19") (pintype "bidirectional"))
    )
    (net (code "37") (name "/D4") (class "Default")
      (node (ref "JP1") (pin "5") (pinfunction "5_5") (pintype "passive"))
      (node (ref "R13") (pin "2") (pinfunction "2_2") (pintype "passive"))
    )
    (net (code "38") (name "/D4_IN") (class "Default")
      (node (ref "D13") (pin "3") (pinfunction "C_3") (pintype "passive"))
      (node (ref "R13") (pin "1") (pinfunction "1_1") (pintype "passive"))
      (node (ref "U17") (pin "8") (pinfunction "PE6_8") (pintype "bidirectional"))
    )
    (net (code "39") (name "/D5") (class "Default")
      (node (ref "JP1") (pin "6") (pinfunction "6_6") (pintype "passive"))
      (node (ref "R14") (pin "2") (pinfunction "2_2") (pintype "passive"))
    )
    (net (code "40") (name "/D5_IN") (class "Default")
      (node (ref "D14") (pin "3") (pinfunction "C_3") (pintype "passive"))
      (node (ref "R14") (pin "1") (pinfunction "1_1") (pintype "passive"))
      (node (ref "U17") (pin "15") (pinfunction "PB5(OC1A)_15") (pintype "bidirectional"))
    )
    (net (code "41") (name "/D6") (class "Default")
      (node (ref "JP1") (pin "7") (pinfunction "7_7") (pintype "passive"))
      (node (ref "R15") (pin "2") (pinfunction "2_2") (pintype "passive"))
    )
    (net (code "42") (name "/D6_IN") (class "Default")
      (node (ref "D15") (pin "3") (pinfunction "C_3") (pintype "passive"))
      (node (ref "R15") (pin "1") (pinfunction "1_1") (pintype "passive"))
      (node (ref "U17") (pin "16") (pinfunction "PB6(OC1B)_16") (pintype "bidirectional"))
    )
    (net (code "43") (name "/D7") (class "Default")
      (node (ref "JP1") (pin "8") (pinfunction "8_8") (pintype "passive"))
      (node (ref "R16") (pin "2") (pinfunction "2_2") (pintype "passive"))
    )
    (net (code "44") (name "/D7_IN") (class "Default")
      (node (ref "D22") (pin "3") (pinfunction "C_3") (pintype "passive"))
      (node (ref "R16") (pin "1") (pinfunction "1_1") (pintype "passive"))
      (node (ref "U17") (pin "40") (pinfunction "PC5_40") (pintype "bidirectional"))
    )
    (net (code "45") (name "/D8") (class "Default")
      (node (ref "JP2") (pin "1") (pinfunction "1_1") (pintype "passive"))
      (node (ref "R1") (pin "2") (pinfunction "2_2") (pintype "passive"))
    )
    (net (code "46") (name "/D8_IN") (class "Default")
      (node (ref "D1") (pin "3") (pinfunction "C_3") (pintype "passive"))
      (node (ref "R1") (pin "1") (pinfunction "1_1") (pintype "passive"))
      (node (ref "U17") (pin "41") (pinfunction "PC6_41") (pintype "bidirectional"))
    )
    (net (code "47") (name "/D9") (class "Default")
      (node (ref "JP2") (pin "2") (pinfunction "2_2") (pintype "passive"))
      (node (ref "R2") (pin "2") (pinfunction "2_2") (pintype "passive"))
    )
    (net (code "48") (name "/D9_IN") (class "Default")
      (node (ref "D2") (pin "3") (pinfunction "C_3") (pintype "passive"))
      (node (ref "R2") (pin "1") (pinfunction "1_1") (pintype "passive"))
      (node (ref "U17") (pin "42") (pinfunction "PC7_42") (pintype "bidirectional"))
    )
    (net (code "49") (name "/D10") (class "Default")
      (node (ref "JP2") (pin "3") (pinfunction "3_3") (pintype "passive"))
      (node (ref "R3") (pin "2") (pinfunction "2_2") (pintype "passive"))
    )
    (net (code "50") (name "/D11") (class "Default")
      (node (ref "JP2") (pin "4") (pinfunction "4_4") (pintype "passive"))
      (node (ref "JP8") (pin "4") (pinfunction "4_4") (pintype "bidirectional"))
      (node (ref "R4") (pin "2") (pinfunction "2_2") (pintype "passive"))
    )
    (net (code "51") (name "/D12") (class "Default")
      (node (ref "JP2") (pin "5") (pinfunction "5_5") (pintype "passive"))
      (node (ref "JP8") (pin "1") (pinfunction "1_1") (pintype "bidirectional"))
      (node (ref "R5") (pin "2") (pinfunction "2_2") (pintype "passive"))
    )
    (net (code "52") (name "/D13") (class "Default")
      (node (ref "JP2") (pin "6") (pinfunction "6_6") (pintype "passive"))
      (node (ref "JP8") (pin "3") (pinfunction "3_3") (pintype "bidirectional"))
      (node (ref "R6") (pin "2") (pinfunction "2_2") (pintype "passive"))
    )
    (net (code "53") (name "/DTR") (class "Default")
      (node (ref "C4") (pin "1") (pinfunction "1_1") (pintype "passive"))
      (node (ref "R63") (pin "1") (pinfunction "1_1") (pintype "passive"))
    )
    (net (code "54") (name "/E") (class "Default")
      (node (ref "U$1") (pin "6") (pinfunction "P$6_6") (pintype "bidirectional"))
      (node (ref "U17") (pin "39") (pinfunction "PC4_39") (pintype "bidirectional"))
    )
    (net (code "55") (name "/GND") (class "Default")
      (node (ref "C1") (pin "1") (pinfunction "1_1") (pintype "passive"))
      (node (ref "C10") (pin "2") (pinfunction "2_2") (pintype "passive"))
      (node (ref "C11") (pin "2") (pinfunction "2_2") (pintype "passive"))
      (node (ref "C12") (pin "2") (pinfunction "2_2") (pintype "passive"))
      (node (ref "C13") (pin "2") (pinfunction "2_2") (pintype "passive"))
      (node (ref "C2") (pin "1") (pinfunction "1_1") (pintype "passive"))
      (node (ref "C3") (pin "-") (pinfunction "-_-") (pintype "passive"))
      (node (ref "C5") (pin "2") (pinfunction "2_2") (pintype "passive"))
      (node (ref "C6") (pin "2") (pinfunction "2_2") (pintype "passive"))
      (node (ref "C7") (pin "2") (pinfunction "2_2") (pintype "passive"))
      (node (ref "C8") (pin "2") (pinfunction "2_2") (pintype "passive"))
      (node (ref "C9") (pin "2") (pinfunction "2_2") (pintype "passive"))
      (node (ref "D1") (pin "1") (pinfunction "A_1") (pintype "passive"))
      (node (ref "D10") (pin "1") (pinfunction "A_1") (pintype "passive"))
      (node (ref "D11") (pin "1") (pinfunction "A_1") (pintype "passive"))
      (node (ref "D12") (pin "1") (pinfunction "A_1") (pintype "passive"))
      (node (ref "D13") (pin "1") (pinfunction "A_1") (pintype "passive"))
      (node (ref "D14") (pin "1") (pinfunction "A_1") (pintype "passive"))
      (node (ref "D15") (pin "1") (pinfunction "A_1") (pintype "passive"))
      (node (ref "D16") (pin "1") (pinfunction "A_1") (pintype "passive"))
      (node (ref "D17") (pin "1") (pinfunction "A_1") (pintype "passive"))
      (node (ref "D18") (pin "1") (pinfunction "A_1") (pintype "passive"))
      (node (ref "D19") (pin "1") (pinfunction "A_1") (pintype "passive"))
      (node (ref "D2") (pin "1") (pinfunction "A_1") (pintype "passive"))
      (node (ref "D20") (pin "1") (pinfunction "A_1") (pintype "passive"))
      (node (ref "D21") (pin "1") (pinfunction "A_1") (pintype "passive"))
      (node (ref "D22") (pin "1") (pinfunction "A_1") (pintype "passive"))
      (node (ref "D26") (pin "1") (pinfunction "A_1") (pintype "passive"))
      (node (ref "D27") (pin "1") (pinfunction "A_1") (pintype "passive"))
      (node (ref "D28") (pin "1") (pinfunction "A_1") (pintype "passive"))
      (node (ref "D29") (pin "1") (pinfunction "A_1") (pintype "passive"))
      (node (ref "D3") (pin "1") (pinfunction "A_1") (pintype "passive"))
      (node (ref "D32") (pin "1") (pinfunction "A_1") (pintype "passive"))
      (node (ref "D4") (pin "1") (pinfunction "A_1") (pintype "passive"))
      (node (ref "D5") (pin "1") (pinfunction "A_1") (pintype "passive"))
      (node (ref "D6") (pin "1") (pinfunction "A_1") (pintype "passive"))
      (node (ref "D7") (pin "1") (pinfunction "A_1") (pintype "passive"))
      (node (ref "D8") (pin "1") (pinfunction "A_1") (pintype "passive"))
      (node (ref "D9") (pin "1") (pinfunction "A_1") (pintype "passive"))
      (node (ref "IR") (pin "3") (pinfunction "3_3") (pintype "passive"))
      (node (ref "J1") (pin "GND") (pinfunction "GND_GND") (pintype "bidirectional"))
      (node (ref "J1") (pin "GNDBREAK") (pinfunction "GNDBREAK_GNDBREAK") (pintype "bidirectional"))
      (node (ref "JP10") (pin "5") (pinfunction "5_5") (pintype "bidirectional"))
      (node (ref "JP10") (pin "6") (pinfunction "6_6") (pintype "bidirectional"))
      (node (ref "JP11") (pin "5") (pinfunction "5_5") (pintype "bidirectional"))
      (node (ref "JP11") (pin "6") (pinfunction "6_6") (pintype "bidirectional"))
      (node (ref "JP2") (pin "7") (pinfunction "7_7") (pintype "passive"))
      (node (ref "JP4") (pin "6") (pinfunction "6_6") (pintype "passive"))
      (node (ref "JP4") (pin "7") (pinfunction "7_7") (pintype "passive"))
      (node (ref "JP7") (pin "1") (pinfunction "1_1") (pintype "passive"))
      (node (ref "JP7") (pin "2") (pinfunction "2_2") (pintype "passive"))
      (node (ref "JP7") (pin "3") (pinfunction "3_3") (pintype "passive"))
      (node (ref "JP7") (pin "4") (pinfunction "4_4") (pintype "passive"))
      (node (ref "JP8") (pin "6") (pinfunction "6_6") (pintype "bidirectional"))
      (node (ref "JP9") (pin "GND") (pinfunction "GND_GND") (pintype "bidirectional"))
      (node (ref "POWER") (pin "P$2") (pinfunction "P$2_P$2") (pintype "bidirectional"))
      (node (ref "R26") (pin "1") (pinfunction "1_1") (pintype "passive"))
      (node (ref "R31") (pin "1") (pinfunction "1_1") (pintype "passive"))
      (node (ref "R32") (pin "1") (pinfunction "1_1") (pintype "passive"))
      (node (ref "R36") (pin "1") (pinfunction "1_1") (pintype "passive"))
      (node (ref "R41") (pin "1") (pinfunction "1_1") (pintype "passive"))
      (node (ref "R46") (pin "1") (pinfunction "1_1") (pintype "passive"))
      (node (ref "R51") (pin "1") (pinfunction "1_1") (pintype "passive"))
      (node (ref "R52") (pin "1") (pinfunction "1_1") (pintype "passive"))
      (node (ref "R53") (pin "1") (pinfunction "1_1") (pintype "passive"))
      (node (ref "R54") (pin "1") (pinfunction "1_1") (pintype "passive"))
      (node (ref "R62") (pin "1") (pinfunction "1_1") (pintype "passive"))
      (node (ref "R65") (pin "2") (pinfunction "2_2") (pintype "passive"))
      (node (ref "RESET") (pin "1") (pinfunction "1_1") (pintype "passive"))
      (node (ref "RESET") (pin "2") (pinfunction "2_2") (pintype "passive"))
      (node (ref "S2") (pin "1") (pinfunction "1_1") (pintype "passive"))
      (node (ref "S2") (pin "2") (pinfunction "2_2") (pintype "passive"))
      (node (ref "U$1") (pin "1") (pinfunction "P$1_1") (pintype "bidirectional"))
      (node (ref "U$1") (pin "5") (pinfunction "P$5_5") (pintype "bidirectional"))
      (node (ref "U$11") (pin "2") (pinfunction "S_2") (pintype "bidirectional"))
      (node (ref "U$2") (pin "3") (pinfunction "E_3") (pintype "passive"))
      (node (ref "U$3") (pin "GND@N1") (pinfunction "PGND_GND@N1") (pintype "bidirectional"))
      (node (ref "U$3") (pin "GND@N2") (pinfunction "PGND_GND@N2") (pintype "bidirectional"))
      (node (ref "U$3") (pin "GND@N3") (pinfunction "PGND_GND@N3") (pintype "bidirectional"))
      (node (ref "U$3") (pin "GND@N4") (pinfunction "PGND_GND@N4") (pintype "bidirectional"))
      (node (ref "U$3") (pin "GND@N5") (pinfunction "PGND_GND@N5") (pintype "bidirectional"))
      (node (ref "U$3") (pin "GND@N6") (pinfunction "PGND_GND@N6") (pintype "bidirectional"))
      (node (ref "U$3") (pin "GND@N7") (pinfunction "PGND_GND@N7") (pintype "bidirectional"))
      (node (ref "U$3") (pin "GND@N8") (pinfunction "PGND_GND@N8") (pintype "bidirectional"))
      (node (ref "U$3") (pin "P$11") (pinfunction "PGND_P$11") (pintype "bidirectional"))
      (node (ref "U$3") (pin "P$4") (pinfunction "PS/SYNC_P$4") (pintype "bidirectional"))
      (node (ref "U$3") (pin "P$7") (pinfunction "GND_P$7") (pintype "bidirectional"))
      (node (ref "U$5") (pin "3") (pinfunction "ANODE_3") (pintype "bidirectional"))
      (node (ref "U$8") (pin "P$10") (pinfunction "GND2_P$10") (pintype "bidirectional"))
      (node (ref "U$8") (pin "P$12") (pinfunction "GND3_P$12") (pintype "bidirectional"))
      (node (ref "U$8") (pin "P$13") (pinfunction "NC3_P$13") (pintype "bidirectional"))
      (node (ref "U$8") (pin "P$5") (pinfunction "GND1_P$5") (pintype "bidirectional"))
      (node (ref "U$8") (pin "P$7") (pinfunction "SA0_P$7") (pintype "bidirectional"))
      (node (ref "U$8") (pin "P$8") (pinfunction "NC2_P$8") (pintype "bidirectional"))
      (node (ref "U1") (pin "18") (pinfunction "GND2_18") (pintype "power_in"))
      (node (ref "U1") (pin "21") (pinfunction "GND3_21") (pintype "power_in"))
      (node (ref "U1") (pin "25") (pinfunction "AGND_25") (pintype "power_in"))
      (node (ref "U1") (pin "26") (pinfunction "TEST_26") (pintype "input"))
      (node (ref "U1") (pin "7") (pinfunction "GND1_7") (pintype "power_in"))
      (node (ref "U10") (pin "GND") (pinfunction "GND_PPAD_GND") (pintype "bidirectional"))
      (node (ref "U10") (pin "P$5") (pinfunction "GND1_P$5") (pintype "bidirectional"))
      (node (ref "U10") (pin "P$6") (pinfunction "GND2_P$6") (pintype "bidirectional"))
      (node (ref "U12") (pin "4") (pinfunction "V-_4") (pintype "power_in"))
      (node (ref "U16") (pin "4") (pinfunction "V-_4") (pintype "power_in"))
      (node (ref "U16") (pin "5") (pinfunction "+IN_5") (pintype "input"))
      (node (ref "U16") (pin "6") (pinfunction "-IN_6") (pintype "input"))
      (node (ref "U17") (pin "22") (pinfunction "GND1_22") (pintype "bidirectional"))
      (node (ref "U17") (pin "53") (pinfunction "GND2_53") (pintype "bidirectional"))
      (node (ref "U17") (pin "63") (pinfunction "GND3_63") (pintype "bidirectional"))
      (node (ref "U4") (pin "13") (pinfunction "GND_13") (pintype "bidirectional"))
      (node (ref "U4") (pin "21") (pinfunction "GND1_21") (pintype "bidirectional"))
      (node (ref "U4") (pin "22") (pinfunction "GND2_22") (pintype "bidirectional"))
      (node (ref "U4") (pin "34") (pinfunction "PIO11_34") (pintype "bidirectional"))
      (node (ref "U7") (pin "P$2") (pinfunction "GND_P$2") (pintype "bidirectional"))
      (node (ref "U8") (pin "P$2") (pinfunction "GND_P$2") (pintype "bidirectional"))
      (node (ref "U9") (pin "GND") (pinfunction "GND_PPAD_GND") (pintype "bidirectional"))
      (node (ref "U9") (pin "P$5") (pinfunction "GND1_P$5") (pintype "bidirectional"))
      (node (ref "U9") (pin "P$6") (pinfunction "GND2_P$6") (pintype "bidirectional"))
    )
    (net (code "56") (name "/IR") (class "Default")
      (node (ref "IR") (pin "1") (pinfunction "1_1") (pintype "passive"))
      (node (ref "U17") (pin "25") (pinfunction "PD0_25") (pintype "bidirectional"))
    )
    (net (code "57") (name "/LCD0") (class "Default")
      (node (ref "R34") (pin "2") (pinfunction "2_2") (pintype "passive"))
      (node (ref "U17") (pin "51") (pinfunction "PA0_51") (pintype "bidirectional"))
    )
    (net (code "58") (name "/LCD1") (class "Default")
      (node (ref "U$1") (pin "8") (pinfunction "P$8_8") (pintype "bidirectional"))
      (node (ref "U17") (pin "50") (pinfunction "PA1_50") (pintype "bidirectional"))
    )
    (net (code "59") (name "/LCD2") (class "Default")
      (node (ref "U$1") (pin "9") (pinfunction "P$9_9") (pintype "bidirectional"))
      (node (ref "U17") (pin "49") (pinfunction "PA2_49") (pintype "bidirectional"))
    )
    (net (code "60") (name "/LCD3") (class "Default")
      (node (ref "U$1") (pin "10") (pinfunction "P$10_10") (pintype "bidirectional"))
      (node (ref "U17") (pin "48") (pinfunction "PA3_48") (pintype "bidirectional"))
    )
    (net (code "61") (name "/LCD4") (class "Default")
      (node (ref "U$1") (pin "11") (pinfunction "P$11_11") (pintype "bidirectional"))
      (node (ref "U17") (pin "47") (pinfunction "PA4_47") (pintype "bidirectional"))
    )
    (net (code "62") (name "/LCD5") (class "Default")
      (node (ref "U$1") (pin "12") (pinfunction "P$12_12") (pintype "bidirectional"))
      (node (ref "U17") (pin "46") (pinfunction "PA5_46") (pintype "bidirectional"))
    )
    (net (code "63") (name "/LCD6") (class "Default")
      (node (ref "U$1") (pin "13") (pinfunction "P$13_13") (pintype "bidirectional"))
      (node (ref "U17") (pin "45") (pinfunction "PA6_45") (pintype "bidirectional"))
    )
    (net (code "64") (name "/LCD7") (class "Default")
      (node (ref "U$1") (pin "14") (pinfunction "P$14_14") (pintype "bidirectional"))
      (node (ref "U17") (pin "44") (pinfunction "PA7_44") (pintype "bidirectional"))
    )
    (net (code "65") (name "/LED0") (class "Default")
      (node (ref "D30") (pin "A") (pinfunction "A_A") (pintype "passive"))
      (node (ref "U17") (pin "34") (pinfunction "PG1_34") (pintype "bidirectional"))
    )
    (net (code "66") (name "/LED1") (class "Default")
      (node (ref "D31") (pin "A") (pinfunction "A_A") (pintype "passive"))
      (node (ref "U17") (pin "33") (pinfunction "PG0_33") (pintype "bidirectional"))
    )
    (net (code "67") (name "/M0_DIR0") (class "Default")
      (node (ref "U17") (pin "29") (pinfunction "PD4_29") (pintype "bidirectional"))
      (node (ref "U9") (pin "P$9") (pinfunction "IN1_P$9") (pintype "bidirectional"))
    )
    (net (code "68") (name "/M0_DIR1") (class "Default")
      (node (ref "U17") (pin "30") (pinfunction "PD5_30") (pintype "bidirectional"))
      (node (ref "U9") (pin "P$11") (pinfunction "IN2_P$11") (pintype "bidirectional"))
    )
    (net (code "69") (name "/M0_EN") (class "Default")
      (node (ref "U17") (pin "14") (pinfunction "PB4(OC0A)_14") (pintype "bidirectional"))
      (node (ref "U9") (pin "P$10") (pinfunction "EN1_P$10") (pintype "bidirectional"))
      (node (ref "U9") (pin "P$12") (pinfunction "EN2_P$12") (pintype "bidirectional"))
    )
    (net (code "70") (name "/M1_DIR0") (class "Default")
      (node (ref "U10") (pin "P$9") (pinfunction "IN1_P$9") (pintype "bidirectional"))
      (node (ref "U17") (pin "31") (pinfunction "PD6_31") (pintype "bidirectional"))
    )
    (net (code "71") (name "/M1_DIR1") (class "Default")
      (node (ref "U10") (pin "P$11") (pinfunction "IN2_P$11") (pintype "bidirectional"))
      (node (ref "U17") (pin "32") (pinfunction "PD7_32") (pintype "bidirectional"))
    )
    (net (code "72") (name "/M1_EN") (class "Default")
      (node (ref "U10") (pin "P$10") (pinfunction "EN1_P$10") (pintype "bidirectional"))
      (node (ref "U10") (pin "P$12") (pinfunction "EN2_P$12") (pintype "bidirectional"))
      (node (ref "U17") (pin "17") (pinfunction "PB7(OC2A)_17") (pintype "bidirectional"))
    )
    (net (code "73") (name "/MISO") (class "Default")
      (node (ref "D5") (pin "3") (pinfunction "C_3") (pintype "passive"))
      (node (ref "R5") (pin "1") (pinfunction "1_1") (pintype "passive"))
      (node (ref "U17") (pin "13") (pinfunction "PB3(MISO)_13") (pintype "bidirectional"))
    )
    (net (code "74") (name "/MOSI") (class "Default")
      (node (ref "D4") (pin "3") (pinfunction "C_3") (pintype "passive"))
      (node (ref "R4") (pin "1") (pinfunction "1_1") (pintype "passive"))
      (node (ref "U17") (pin "12") (pinfunction "PB2(MOSI)_12") (pintype "bidirectional"))
    )
    (net (code "75") (name "/PWR_GATE") (class "Default")
      (node (ref "Q1") (pin "3") (pinfunction "D_3") (pintype "bidirectional"))
      (node (ref "R32") (pin "2") (pinfunction "2_2") (pintype "passive"))
      (node (ref "U$6") (pin "G1") (pinfunction "G1_G1") (pintype "bidirectional"))
      (node (ref "U$6") (pin "G2") (pinfunction "G2_G2") (pintype "bidirectional"))
    )
    (net (code "76") (name "/PWR_SW") (class "Default")
      (node (ref "Q2") (pin "2") (pinfunction "S_2") (pintype "bidirectional"))
      (node (ref "R44") (pin "1") (pinfunction "1_1") (pintype "passive"))
      (node (ref "U$6") (pin "S2") (pinfunction "S2_S2") (pintype "bidirectional"))
      (node (ref "U$7") (pin "S2") (pinfunction "S2_S2") (pintype "bidirectional"))
    )
    (net (code "77") (name "/RESET") (class "Default")
      (node (ref "C4") (pin "2") (pinfunction "2_2") (pintype "passive"))
      (node (ref "R39") (pin "1") (pinfunction "1_1") (pintype "passive"))
      (node (ref "R40") (pin "2") (pinfunction "2_2") (pintype "passive"))
      (node (ref "R56") (pin "1") (pinfunction "1_1") (pintype "passive"))
      (node (ref "RESET") (pin "3") (pinfunction "3_3") (pintype "passive"))
      (node (ref "RESET") (pin "4") (pinfunction "4_4") (pintype "passive"))
      (node (ref "U17") (pin "20") (pinfunction "RESET/PG5_20") (pintype "bidirectional"))
    )
    (net (code "78") (name "/RS") (class "Default")
      (node (ref "R33") (pin "1") (pinfunction "1_1") (pintype "passive"))
      (node (ref "U17") (pin "54") (pinfunction "PF7(ADC7)_54") (pintype "bidirectional"))
    )
    (net (code "79") (name "/RX") (class "Default")
      (node (ref "U1") (pin "1") (pinfunction "TXD_1") (pintype "output"))
      (node (ref "U17") (pin "28") (pinfunction "PD3_28") (pintype "bidirectional"))
    )
    (net (code "80") (name "/SCK") (class "Default")
      (node (ref "D6") (pin "3") (pinfunction "C_3") (pintype "passive"))
      (node (ref "R6") (pin "1") (pinfunction "1_1") (pintype "passive"))
      (node (ref "U17") (pin "11") (pinfunction "PB1(SCK)_11") (pintype "bidirectional"))
    )
    (net (code "81") (name "/SCL0") (class "Default")
      (node (ref "JP2") (pin "9") (pinfunction "9_9") (pintype "passive"))
      (node (ref "R7") (pin "2") (pinfunction "2_2") (pintype "passive"))
    )
    (net (code "82") (name "/SCL_5V") (class "Default")
      (node (ref "R60") (pin "1") (pinfunction "1_1") (pintype "passive"))
      (node (ref "U$10") (pin "3") (pinfunction "D_3") (pintype "bidirectional"))
      (node (ref "U17") (pin "6") (pinfunction "PE4(SCL)_6") (pintype "bidirectional"))
    )
    (net (code "83") (name "/SCL_IN") (class "Default")
      (node (ref "D7") (pin "3") (pinfunction "C_3") (pintype "passive"))
      (node (ref "R38") (pin "1") (pinfunction "1_1") (pintype "passive"))
      (node (ref "R7") (pin "1") (pinfunction "1_1") (pintype "passive"))
      (node (ref "U$10") (pin "2") (pinfunction "S_2") (pintype "bidirectional"))
      (node (ref "U$8") (pin "P$4") (pinfunction "SCL_P$4") (pintype "bidirectional"))
    )
    (net (code "84") (name "/SDA0") (class "Default")
      (node (ref "JP2") (pin "10") (pinfunction "10_10") (pintype "passive"))
      (node (ref "R8") (pin "2") (pinfunction "2_2") (pintype "passive"))
    )
    (net (code "85") (name "/SDA_5V") (class "Default")
      (node (ref "R58") (pin "1") (pinfunction "1_1") (pintype "passive"))
      (node (ref "U$9") (pin "3") (pinfunction "D_3") (pintype "bidirectional"))
      (node (ref "U17") (pin "7") (pinfunction "PE5(SDA)_7") (pintype "bidirectional"))
    )
    (net (code "86") (name "/SDA_IN") (class "Default")
      (node (ref "D8") (pin "3") (pinfunction "C_3") (pintype "passive"))
      (node (ref "R37") (pin "1") (pinfunction "1_1") (pintype "passive"))
      (node (ref "R8") (pin "1") (pinfunction "1_1") (pintype "passive"))
      (node (ref "U$8") (pin "P$6") (pinfunction "SDA_P$6") (pintype "bidirectional"))
      (node (ref "U$9") (pin "2") (pinfunction "S_2") (pintype "bidirectional"))
    )
    (net (code "87") (name "/SERVO0") (class "Default")
      (node (ref "JP3") (pin "1") (pinfunction "1_1") (pintype "passive"))
      (node (ref "R47") (pin "2") (pinfunction "2_2") (pintype "passive"))
    )
    (net (code "88") (name "/SERVO0_IN") (class "Default")
      (node (ref "D26") (pin "3") (pinfunction "C_3") (pintype "passive"))
      (node (ref "R47") (pin "1") (pinfunction "1_1") (pintype "passive"))
      (node (ref "U17") (pin "35") (pinfunction "PC0_35") (pintype "bidirectional"))
    )
    (net (code "89") (name "/SERVO1") (class "Default")
      (node (ref "JP3") (pin "2") (pinfunction "2_2") (pintype "passive"))
      (node (ref "R48") (pin "2") (pinfunction "2_2") (pintype "passive"))
    )
    (net (code "90") (name "/SERVO1_IN") (class "Default")
      (node (ref "D27") (pin "3") (pinfunction "C_3") (pintype "passive"))
      (node (ref "R48") (pin "1") (pinfunction "1_1") (pintype "passive"))
      (node (ref "U17") (pin "36") (pinfunction "PC1_36") (pintype "bidirectional"))
    )
    (net (code "91") (name "/SERVO2") (class "Default")
      (node (ref "JP3") (pin "3") (pinfunction "3_3") (pintype "passive"))
      (node (ref "R49") (pin "2") (pinfunction "2_2") (pintype "passive"))
    )
    (net (code "92") (name "/SERVO2_IN") (class "Default")
      (node (ref "D28") (pin "3") (pinfunction "C_3") (pintype "passive"))
      (node (ref "R49") (pin "1") (pinfunction "1_1") (pintype "passive"))
      (node (ref "U17") (pin "37") (pinfunction "PC2_37") (pintype "bidirectional"))
    )
    (net (code "93") (name "/SERVO3") (class "Default")
      (node (ref "JP3") (pin "4") (pinfunction "4_4") (pintype "passive"))
      (node (ref "R50") (pin "2") (pinfunction "2_2") (pintype "passive"))
    )
    (net (code "94") (name "/SERVO3_IN") (class "Default")
      (node (ref "D29") (pin "3") (pinfunction "C_3") (pintype "passive"))
      (node (ref "R50") (pin "1") (pinfunction "1_1") (pintype "passive"))
      (node (ref "U17") (pin "38") (pinfunction "PC3_38") (pintype "bidirectional"))
    )
    (net (code "95") (name "/SS") (class "Default")
      (node (ref "D3") (pin "3") (pinfunction "C_3") (pintype "passive"))
      (node (ref "R3") (pin "1") (pinfunction "1_1") (pintype "passive"))
      (node (ref "U17") (pin "10") (pinfunction "PB0(SS)_10") (pintype "bidirectional"))
    )
    (net (code "96") (name "/SW1") (class "Default")
      (node (ref "S2") (pin "3") (pinfunction "3_3") (pintype "passive"))
      (node (ref "S2") (pin "4") (pinfunction "4_4") (pintype "passive"))
      (node (ref "U17") (pin "9") (pinfunction "PE7_9") (pintype "bidirectional"))
    )
    (net (code "97") (name "/TX") (class "Default")
      (node (ref "U1") (pin "5") (pinfunction "RXD_5") (pintype "input"))
      (node (ref "U17") (pin "27") (pinfunction "PD2_27") (pintype "bidirectional"))
    )
    (net (code "98") (name "/USBGATE") (class "Default")
      (node (ref "Q1") (pin "1") (pinfunction "G_1") (pintype "bidirectional"))
      (node (ref "R42") (pin "1") (pinfunction "1_1") (pintype "passive"))
      (node (ref "U$7") (pin "G1") (pinfunction "G1_G1") (pintype "bidirectional"))
      (node (ref "U$7") (pin "G2") (pinfunction "G2_G2") (pintype "bidirectional"))
      (node (ref "U16") (pin "1") (pinfunction "OUT_1") (pintype "output"))
    )
    (net (code "99") (name "/USB_5V") (class "Default")
      (node (ref "D24") (pin "2") (pinfunction "A2_2") (pintype "passive"))
      (node (ref "F2") (pin "2") (pinfunction "2_2") (pintype "passive"))
      (node (ref "R54") (pin "2") (pinfunction "2_2") (pintype "passive"))
      (node (ref "R55") (pin "1") (pinfunction "1_1") (pintype "passive"))
      (node (ref "U$7") (pin "S1") (pinfunction "S1_S1") (pintype "bidirectional"))
      (node (ref "U1") (pin "20") (pinfunction "VCC_20") (pintype "power_in"))
      (node (ref "U1") (pin "4") (pinfunction "VCCIO_4") (pintype "power_in"))
      (node (ref "U16") (pin "8") (pinfunction "V+_8") (pintype "power_in"))
    )
    (net (code "100") (name "/VIN") (class "Default")
      (node (ref "F1") (pin "1") (pinfunction "1_1") (pintype "passive"))
      (node (ref "J1") (pin "PWR") (pinfunction "PWR_PWR") (pintype "bidirectional"))
      (node (ref "R35") (pin "2") (pinfunction "2_2") (pintype "passive"))
    )
    (net (code "101") (name "/VIN1") (class "Default")
      (node (ref "D24") (pin "1") (pinfunction "A1_1") (pintype "passive"))
      (node (ref "F1") (pin "2") (pinfunction "2_2") (pintype "passive"))
      (node (ref "U$6") (pin "S1") (pinfunction "S1_S1") (pintype "bidirectional"))
    )
    (net (code "102") (name "/VIN_F") (class "Default")
      (node (ref "C13") (pin "1") (pinfunction "1_1") (pintype "passive"))
      (node (ref "JP4") (pin "8") (pinfunction "8_8") (pintype "passive"))
      (node (ref "JP6") (pin "1") (pinfunction "1_1") (pintype "passive"))
      (node (ref "JP6") (pin "2") (pinfunction "2_2") (pintype "passive"))
      (node (ref "JP6") (pin "3") (pinfunction "3_3") (pintype "passive"))
      (node (ref "JP6") (pin "4") (pinfunction "4_4") (pintype "passive"))
      (node (ref "Q2") (pin "3") (pinfunction "D_3") (pintype "bidirectional"))
      (node (ref "R45") (pin "2") (pinfunction "2_2") (pintype "passive"))
      (node (ref "U$3") (pin "P$2") (pinfunction "VIN_P$2") (pintype "bidirectional"))
      (node (ref "U$3") (pin "P$3") (pinfunction "EN_P$3") (pintype "bidirectional"))
      (node (ref "U10") (pin "P$1") (pinfunction "VM1_P$1") (pintype "bidirectional"))
      (node (ref "U10") (pin "P$2") (pinfunction "VM2_P$2") (pintype "bidirectional"))
      (node (ref "U9") (pin "P$1") (pinfunction "VM1_P$1") (pintype "bidirectional"))
      (node (ref "U9") (pin "P$2") (pinfunction "VM2_P$2") (pintype "bidirectional"))
    )
    (net (code "103") (name "/VREG_OUT") (class "Default")
      (node (ref "C11") (pin "1") (pinfunction "1_1") (pintype "passive"))
      (node (ref "C12") (pin "1") (pinfunction "1_1") (pintype "passive"))
      (node (ref "F3") (pin "1") (pinfunction "1_1") (pintype "passive"))
      (node (ref "U$3") (pin "P$8") (pinfunction "FB_P$8") (pintype "bidirectional"))
      (node (ref "U$3") (pin "P$9") (pinfunction "VOUT_P$9") (pintype "bidirectional"))
    )
    (net (code "104") (name "Net-(D23-PadA)") (class "Default")
      (node (ref "D23") (pin "A") (pinfunction "A_A") (pintype "passive"))
      (node (ref "R29") (pin "2") (pinfunction "2_2") (pintype "passive"))
    )
    (net (code "105") (name "Net-(D24-CC)") (class "Default")
      (node (ref "D24") (pin "3") (pinfunction "CC_3") (pintype "passive"))
      (node (ref "Q1") (pin "2") (pinfunction "S_2") (pintype "bidirectional"))
      (node (ref "R23") (pin "2") (pinfunction "2_2") (pintype "passive"))
      (node (ref "R42") (pin "2") (pinfunction "2_2") (pintype "passive"))
    )
    (net (code "106") (name "Net-(D25-PadC)") (class "Default")
      (node (ref "D25") (pin "C") (pinfunction "C_C") (pintype "passive"))
      (node (ref "R41") (pin "2") (pinfunction "2_2") (pintype "passive"))
    )
    (net (code "107") (name "Net-(D30-PadC)") (class "Default")
      (node (ref "D30") (pin "C") (pinfunction "C_C") (pintype "passive"))
      (node (ref "R51") (pin "2") (pinfunction "2_2") (pintype "passive"))
    )
    (net (code "108") (name "Net-(D31-PadC)") (class "Default")
      (node (ref "D31") (pin "C") (pinfunction "C_C") (pintype "passive"))
      (node (ref "R52") (pin "2") (pinfunction "2_2") (pintype "passive"))
    )
    (net (code "109") (name "Net-(D34-PadA)") (class "Default")
      (node (ref "D34") (pin "A") (pinfunction "A_A") (pintype "passive"))
      (node (ref "R57") (pin "2") (pinfunction "2_2") (pintype "passive"))
    )
    (net (code "110") (name "Net-(F2-Pad1)") (class "Default")
      (node (ref "F2") (pin "1") (pinfunction "1_1") (pintype "passive"))
      (node (ref "JP9") (pin "VBUS") (pinfunction "VBUS_VBUS") (pintype "bidirectional"))
    )
    (net (code "111") (name "Net-(JP4-Pad3)") (class "Default")
      (node (ref "JP4") (pin "3") (pinfunction "3_3") (pintype "passive"))
      (node (ref "R56") (pin "2") (pinfunction "2_2") (pintype "passive"))
    )
    (net (code "112") (name "Net-(JP8-Pad5)") (class "Default")
      (node (ref "JP8") (pin "5") (pinfunction "5_5") (pintype "bidirectional"))
      (node (ref "R39") (pin "2") (pinfunction "2_2") (pintype "passive"))
    )
    (net (code "113") (name "Net-(POWER-PadP$1)") (class "Default")
      (node (ref "POWER") (pin "P$1") (pinfunction "P$1_P$1") (pintype "bidirectional"))
      (node (ref "R43") (pin "2") (pinfunction "2_2") (pintype "passive"))
    )
    (net (code "114") (name "Net-(Q2-G)") (class "Default")
      (node (ref "Q2") (pin "1") (pinfunction "G_1") (pintype "bidirectional"))
      (node (ref "R43") (pin "1") (pinfunction "1_1") (pintype "passive"))
      (node (ref "R44") (pin "2") (pinfunction "2_2") (pintype "passive"))
    )
    (net (code "115") (name "Net-(Q3-G)") (class "Default")
      (node (ref "Q3") (pin "1") (pinfunction "G_1") (pintype "bidirectional"))
      (node (ref "R25") (pin "1") (pinfunction "1_1") (pintype "passive"))
      (node (ref "U12") (pin "7") (pinfunction "OUT_7") (pintype "output"))
    )
    (net (code "116") (name "Net-(Q4-G)") (class "Default")
      (node (ref "Q4") (pin "1") (pinfunction "G_1") (pintype "bidirectional"))
      (node (ref "R30") (pin "1") (pinfunction "1_1") (pintype "passive"))
      (node (ref "U12") (pin "1") (pinfunction "OUT_1") (pintype "output"))
    )
    (net (code "117") (name "Net-(U$1-P$3)") (class "Default")
      (node (ref "U$1") (pin "3") (pinfunction "P$3_3") (pintype "bidirectional"))
      (node (ref "U$2") (pin "2") (pinfunction "S_2") (pintype "passive"))
    )
    (net (code "118") (name "Net-(U$1-P$4)") (class "Default")
      (node (ref "R33") (pin "2") (pinfunction "2_2") (pintype "passive"))
      (node (ref "U$1") (pin "4") (pinfunction "P$4_4") (pintype "bidirectional"))
    )
    (net (code "119") (name "Net-(U$1-P$7)") (class "Default")
      (node (ref "R34") (pin "1") (pinfunction "1_1") (pintype "passive"))
      (node (ref "U$1") (pin "7") (pinfunction "P$7_7") (pintype "bidirectional"))
    )
    (net (code "120") (name "Net-(U$3-L1)") (class "Default")
      (node (ref "U$3") (pin "P$1") (pinfunction "L1_P$1") (pintype "bidirectional"))
      (node (ref "U$4") (pin "P$1") (pinfunction "1_P$1") (pintype "passive"))
    )
    (net (code "121") (name "Net-(U$3-L2)") (class "Default")
      (node (ref "U$3") (pin "P$10") (pinfunction "L2_P$10") (pintype "bidirectional"))
      (node (ref "U$4") (pin "P$2") (pinfunction "2_P$2") (pintype "passive"))
    )
    (net (code "122") (name "Net-(U$3-PG)") (class "Default")
      (node (ref "R28") (pin "2") (pinfunction "2_2") (pintype "passive"))
      (node (ref "U$3") (pin "P$5") (pinfunction "PG_P$5") (pintype "bidirectional"))
    )
    (net (code "123") (name "Net-(U$3-VAUX)") (class "Default")
      (node (ref "C10") (pin "1") (pinfunction "1_1") (pintype "passive"))
      (node (ref "U$3") (pin "P$6") (pinfunction "VAUX_P$6") (pintype "bidirectional"))
    )
    (net (code "124") (name "Net-(U$6-D1-PadD1@1)") (class "Default")
      (node (ref "U$6") (pin "D1@1") (pinfunction "D1_D1@1") (pintype "bidirectional"))
      (node (ref "U$6") (pin "D1@2") (pinfunction "D1_D1@2") (pintype "bidirectional"))
      (node (ref "U$6") (pin "D2@1") (pinfunction "D2_D2@1") (pintype "bidirectional"))
      (node (ref "U$6") (pin "D2@2") (pinfunction "D2_D2@2") (pintype "bidirectional"))
    )
    (net (code "125") (name "Net-(U$7-D1-PadD1@1)") (class "Default")
      (node (ref "U$7") (pin "D1@1") (pinfunction "D1_D1@1") (pintype "bidirectional"))
      (node (ref "U$7") (pin "D1@2") (pinfunction "D1_D1@2") (pintype "bidirectional"))
      (node (ref "U$7") (pin "D2@1") (pinfunction "D2_D2@1") (pintype "bidirectional"))
      (node (ref "U$7") (pin "D2@2") (pinfunction "D2_D2@2") (pintype "bidirectional"))
    )
    (net (code "126") (name "Net-(U$8-BYP)") (class "Default")
      (node (ref "C5") (pin "1") (pinfunction "1_1") (pintype "passive"))
      (node (ref "U$8") (pin "P$2") (pinfunction "BYP_P$2") (pintype "bidirectional"))
    )
    (net (code "127") (name "Net-(U1-DTR)") (class "Default")
      (node (ref "R63") (pin "2") (pinfunction "2_2") (pintype "passive"))
      (node (ref "U1") (pin "2") (pinfunction "DTR_2") (pintype "bidirectional"))
    )
    (net (code "128") (name "Net-(U1-RXLED)") (class "Default")
      (node (ref "D34") (pin "C") (pinfunction "C_C") (pintype "passive"))
      (node (ref "U1") (pin "22") (pinfunction "RXLED_22") (pintype "bidirectional"))
    )
    (net (code "129") (name "Net-(U1-TXLED)") (class "Default")
      (node (ref "D23") (pin "C") (pinfunction "C_C") (pintype "passive"))
      (node (ref "U1") (pin "23") (pinfunction "TXLED_23") (pintype "bidirectional"))
    )
    (net (code "130") (name "Net-(U1-USBDM)") (class "Default")
      (node (ref "JP9") (pin "D-") (pinfunction "D-_D-") (pintype "bidirectional"))
      (node (ref "U1") (pin "16") (pinfunction "USBDM_16") (pintype "bidirectional"))
    )
    (net (code "131") (name "Net-(U1-USBDP)") (class "Default")
      (node (ref "JP9") (pin "D+") (pinfunction "D+_D+") (pintype "bidirectional"))
      (node (ref "U1") (pin "15") (pinfunction "USBDP_15") (pintype "bidirectional"))
    )
    (net (code "132") (name "Net-(U4-RX)") (class "Default")
      (node (ref "R61") (pin "1") (pinfunction "1_1") (pintype "passive"))
      (node (ref "R62") (pin "2") (pinfunction "2_2") (pintype "passive"))
      (node (ref "U4") (pin "2") (pinfunction "RX_2") (pintype "bidirectional"))
    )
    (net (code "133") (name "Net-(U8-EN)") (class "Default")
      (node (ref "R65") (pin "1") (pinfunction "1_1") (pintype "passive"))
      (node (ref "U8") (pin "P$3") (pinfunction "EN_P$3") (pintype "bidirectional"))
    )
    (net (code "134") (name "Net-(U8-ILIM)") (class "Default")
      (node (ref "R53") (pin "2") (pinfunction "2_2") (pintype "passive"))
      (node (ref "U8") (pin "P$5") (pinfunction "ILIM_P$5") (pintype "bidirectional"))
    )
    (net (code "135") (name "Net-(U12A-+IN)") (class "Default")
      (node (ref "R27") (pin "1") (pinfunction "1_1") (pintype "passive"))
      (node (ref "R31") (pin "2") (pinfunction "2_2") (pintype "passive"))
      (node (ref "U12") (pin "3") (pinfunction "+IN_3") (pintype "input"))
    )
    (net (code "136") (name "Net-(U12B-+IN)") (class "Default")
      (node (ref "R24") (pin "1") (pinfunction "1_1") (pintype "passive"))
      (node (ref "R26") (pin "2") (pinfunction "2_2") (pintype "passive"))
      (node (ref "U12") (pin "5") (pinfunction "+IN_5") (pintype "input"))
    )
    (net (code "137") (name "Net-(U16A-+IN)") (class "Default")
      (node (ref "R35") (pin "1") (pinfunction "1_1") (pintype "passive"))
      (node (ref "R36") (pin "2") (pinfunction "2_2") (pintype "passive"))
      (node (ref "U16") (pin "3") (pinfunction "+IN_3") (pintype "input"))
    )
    (net (code "138") (name "Net-(U17-PF6(ADC6))") (class "Default")
      (node (ref "R45") (pin "1") (pinfunction "1_1") (pintype "passive"))
      (node (ref "R46") (pin "2") (pinfunction "2_2") (pintype "passive"))
      (node (ref "U17") (pin "55") (pinfunction "PF6(ADC6)_55") (pintype "bidirectional"))
    )
    (net (code "139") (name "Net-(U17-PG2)") (class "Default")
      (node (ref "R55") (pin "2") (pinfunction "2_2") (pintype "passive"))
      (node (ref "U17") (pin "43") (pinfunction "PG2_43") (pintype "bidirectional"))
    )
    (net (code "140") (name "Net-(U17-XTAL1)") (class "Default")
      (node (ref "C1") (pin "2") (pinfunction "2_2") (pintype "passive"))
      (node (ref "U17") (pin "24") (pinfunction "XTAL1_24") (pintype "bidirectional"))
      (node (ref "Y1") (pin "P$1") (pinfunction "1_P$1") (pintype "passive"))
    )
    (net (code "141") (name "Net-(U17-XTAL2)") (class "Default")
      (node (ref "C2") (pin "2") (pinfunction "2_2") (pintype "passive"))
      (node (ref "U17") (pin "23") (pinfunction "XTAL2_23") (pintype "bidirectional"))
      (node (ref "Y1") (pin "P$2") (pinfunction "2_P$2") (pintype "passive"))
    )
    (net (code "142") (name "unconnected-(JP4-Pad1)") (class "Default")
      (node (ref "JP4") (pin "1") (pinfunction "1_1") (pintype "passive"))
    )
    (net (code "143") (name "unconnected-(JP12-Pad1)") (class "Default")
      (node (ref "JP12") (pin "1") (pinfunction "1_1") (pintype "passive"))
    )
    (net (code "144") (name "unconnected-(JP12-Pad2)") (class "Default")
      (node (ref "JP12") (pin "2") (pinfunction "2_2") (pintype "passive"))
    )
    (net (code "145") (name "unconnected-(U$8-INT2-PadP$9)") (class "Default")
      (node (ref "U$8") (pin "P$9") (pinfunction "INT2_P$9") (pintype "bidirectional"))
    )
    (net (code "146") (name "unconnected-(U$8-NC1-PadP$3)") (class "Default")
      (node (ref "U$8") (pin "P$3") (pinfunction "NC1_P$3") (pintype "bidirectional"))
    )
    (net (code "147") (name "unconnected-(U1-3V3OUT-Pad17)") (class "Default")
      (node (ref "U1") (pin "17") (pinfunction "3V3OUT_17") (pintype "output"))
    )
    (net (code "148") (name "unconnected-(U1-CTS-Pad11)") (class "Default")
      (node (ref "U1") (pin "11") (pinfunction "CTS_11") (pintype "bidirectional"))
    )
    (net (code "149") (name "unconnected-(U1-RTS-Pad3)") (class "Default")
      (node (ref "U1") (pin "3") (pinfunction "RTS_3") (pintype "bidirectional"))
    )
    (net (code "150") (name "unconnected-(U4-AIO0-Pad9)") (class "Default")
      (node (ref "U4") (pin "9") (pinfunction "AIO0_9") (pintype "bidirectional"))
    )
    (net (code "151") (name "unconnected-(U4-AIO1-Pad10)") (class "Default")
      (node (ref "U4") (pin "10") (pinfunction "AIO1_10") (pintype "bidirectional"))
    )
    (net (code "152") (name "unconnected-(U4-CLK-Pad19)") (class "Default")
      (node (ref "U4") (pin "19") (pinfunction "CLK_19") (pintype "bidirectional"))
    )
    (net (code "153") (name "unconnected-(U4-CSB-Pad16)") (class "Default")
      (node (ref "U4") (pin "16") (pinfunction "CSB_16") (pintype "bidirectional"))
    )
    (net (code "154") (name "unconnected-(U4-CTS-Pad3)") (class "Default")
      (node (ref "U4") (pin "3") (pinfunction "CTS_3") (pintype "bidirectional"))
    )
    (net (code "155") (name "unconnected-(U4-MISO-Pad18)") (class "Default")
      (node (ref "U4") (pin "18") (pinfunction "MISO_18") (pintype "bidirectional"))
    )
    (net (code "156") (name "unconnected-(U4-MOSI-Pad17)") (class "Default")
      (node (ref "U4") (pin "17") (pinfunction "MOSI_17") (pintype "bidirectional"))
    )
    (net (code "157") (name "unconnected-(U4-NC-Pad14)") (class "Default")
      (node (ref "U4") (pin "14") (pinfunction "NC_14") (pintype "bidirectional"))
    )
    (net (code "158") (name "unconnected-(U4-PCM_CLK-Pad5)") (class "Default")
      (node (ref "U4") (pin "5") (pinfunction "PCM_CLK_5") (pintype "bidirectional"))
    )
    (net (code "159") (name "unconnected-(U4-PCM_IN-Pad7)") (class "Default")
      (node (ref "U4") (pin "7") (pinfunction "PCM_IN_7") (pintype "bidirectional"))
    )
    (net (code "160") (name "unconnected-(U4-PCM_OUT-Pad6)") (class "Default")
      (node (ref "U4") (pin "6") (pinfunction "PCM_OUT_6") (pintype "bidirectional"))
    )
    (net (code "161") (name "unconnected-(U4-PCN_SYNC-Pad8)") (class "Default")
      (node (ref "U4") (pin "8") (pinfunction "PCN_SYNC_8") (pintype "bidirectional"))
    )
    (net (code "162") (name "unconnected-(U4-PIO0-Pad23)") (class "Default")
      (node (ref "U4") (pin "23") (pinfunction "PIO0_23") (pintype "bidirectional"))
    )
    (net (code "163") (name "unconnected-(U4-PIO1-Pad24)") (class "Default")
      (node (ref "U4") (pin "24") (pinfunction "PIO1_24") (pintype "bidirectional"))
    )
    (net (code "164") (name "unconnected-(U4-PIO2-Pad25)") (class "Default")
      (node (ref "U4") (pin "25") (pinfunction "PIO2_25") (pintype "bidirectional"))
    )
    (net (code "165") (name "unconnected-(U4-PIO3-Pad26)") (class "Default")
      (node (ref "U4") (pin "26") (pinfunction "PIO3_26") (pintype "bidirectional"))
    )
    (net (code "166") (name "unconnected-(U4-PIO4-Pad27)") (class "Default")
      (node (ref "U4") (pin "27") (pinfunction "PIO4_27") (pintype "bidirectional"))
    )
    (net (code "167") (name "unconnected-(U4-PIO5-Pad28)") (class "Default")
      (node (ref "U4") (pin "28") (pinfunction "PIO5_28") (pintype "bidirectional"))
    )
    (net (code "168") (name "unconnected-(U4-PIO6-Pad29)") (class "Default")
      (node (ref "U4") (pin "29") (pinfunction "PIO6_29") (pintype "bidirectional"))
    )
    (net (code "169") (name "unconnected-(U4-PIO7-Pad30)") (class "Default")
      (node (ref "U4") (pin "30") (pinfunction "PIO7_30") (pintype "bidirectional"))
    )
    (net (code "170") (name "unconnected-(U4-PIO8-Pad31)") (class "Default")
      (node (ref "U4") (pin "31") (pinfunction "PIO8_31") (pintype "bidirectional"))
    )
    (net (code "171") (name "unconnected-(U4-PIO9-Pad32)") (class "Default")
      (node (ref "U4") (pin "32") (pinfunction "PIO9_32") (pintype "bidirectional"))
    )
    (net (code "172") (name "unconnected-(U4-PIO10-Pad33)") (class "Default")
      (node (ref "U4") (pin "33") (pinfunction "PIO10_33") (pintype "bidirectional"))
    )
    (net (code "173") (name "unconnected-(U4-RST-Pad11)") (class "Default")
      (node (ref "U4") (pin "11") (pinfunction "RST_11") (pintype "bidirectional"))
    )
    (net (code "174") (name "unconnected-(U4-RTS-Pad4)") (class "Default")
      (node (ref "U4") (pin "4") (pinfunction "RTS_4") (pintype "bidirectional"))
    )
    (net (code "175") (name "unconnected-(U4-VBUSD+-Pad20)") (class "Default")
      (node (ref "U4") (pin "20") (pinfunction "VBUSD+_20") (pintype "bidirectional"))
    )
    (net (code "176") (name "unconnected-(U4-VBUSD--Pad15)") (class "Default")
      (node (ref "U4") (pin "15") (pinfunction "VBUSD-_15") (pintype "bidirectional"))
    )
    (net (code "177") (name "unconnected-(U7-NC-PadP$5)") (class "Default")
      (node (ref "U7") (pin "P$5") (pinfunction "NC_P$5") (pintype "bidirectional"))
    )
    (net (code "178") (name "unconnected-(U8-FAULT-PadP$4)") (class "Default")
      (node (ref "U8") (pin "P$4") (pinfunction "FAULT_P$4") (pintype "bidirectional"))
    )
    (net (code "179") (name "unconnected-(U16B-OUT-Pad7)") (class "Default")
      (node (ref "U16") (pin "7") (pinfunction "OUT_7") (pintype "output"))
    )
    (net (code "180") (name "unconnected-(U17-NC-Pad1)") (class "Default")
      (node (ref "U17") (pin "1") (pinfunction "NC_1") (pintype "bidirectional"))
    )
  )
)
